# SCH_Phyge-V_1.net
KiCad netlist of a schematic drawn in EasyEDA
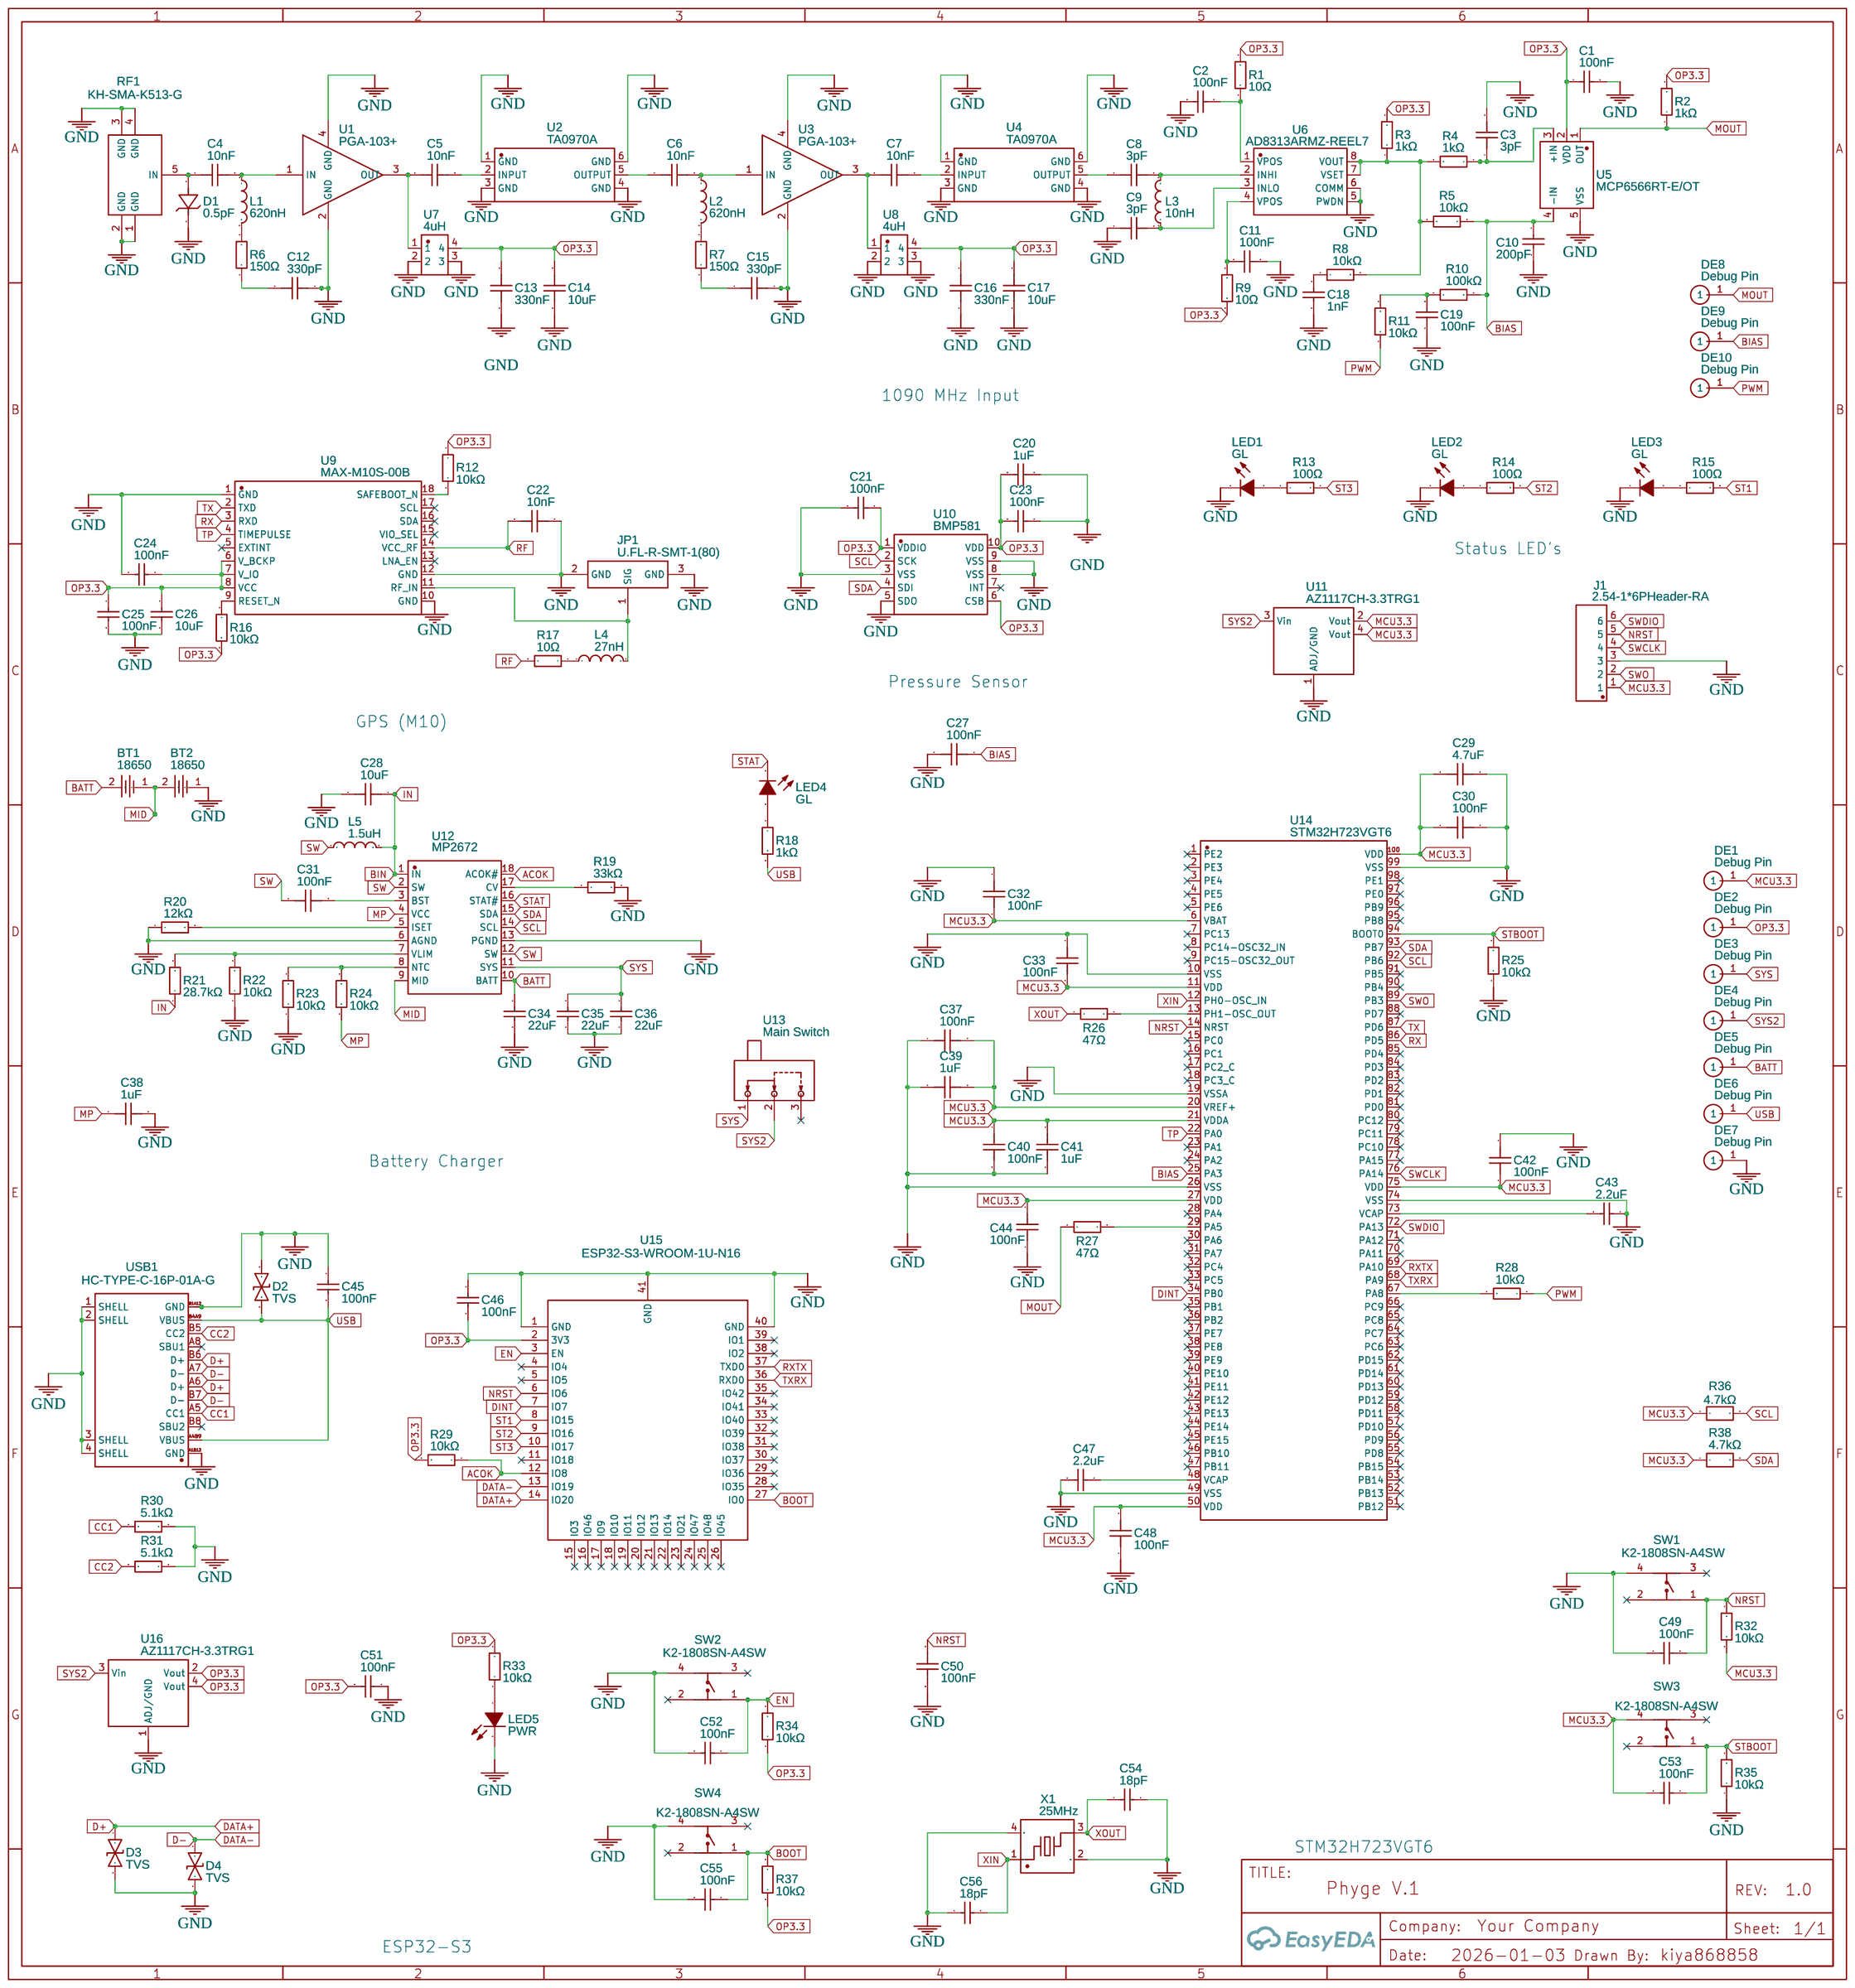
[diagram p0: schematic sheet]

(export (version "E")
  (design (tool "Eeschema 10.0.6"))
  (components
    (comp (ref "BT1")
      (value "18650")
      (fields
        (field (name "Manufacturer Part") "BH-18650-B1BA002")
        (field (name "Manufacturer") "MYOUNG(美阳)")
      )
      (libsource (lib "") (part "BH-18650-B1BA002"))
    )
    (comp (ref "BT2")
      (value "18650")
      (fields
        (field (name "Manufacturer Part") "BH-18650-B1BA002")
        (field (name "Manufacturer") "MYOUNG(美阳)")
      )
      (libsource (lib "") (part "BH-18650-B1BA002"))
    )
    (comp (ref "C1")
      (value "100nF")
      (fields
        (field (name "Manufacturer Part") "CC0603JRX7R9BB104")
        (field (name "Manufacturer") "YAGEO(国巨)")
      )
      (libsource (lib "") (part "CC0603JRX7R9BB104"))
    )
    (comp (ref "C2")
      (value "100nF")
      (fields
        (field (name "Manufacturer Part") "CC0603JRX7R9BB104")
        (field (name "Manufacturer") "YAGEO(国巨)")
      )
      (libsource (lib "") (part "CC0603JRX7R9BB104"))
    )
    (comp (ref "C3")
      (value "3pF")
      (fields (field (name "Manufacturer Part") "CGA3E2C0G1H030CT0Y0N") (field (name "Manufacturer") "TDK"))
      (libsource (lib "") (part "CGA3E2C0G1H030CT0Y0N"))
    )
    (comp (ref "C4")
      (value "10nF")
      (fields
        (field (name "Manufacturer Part") "CC0805JRX7R9BB103")
        (field (name "Manufacturer") "YAGEO(国巨)")
      )
      (libsource (lib "") (part "CC0805JRX7R9BB103"))
    )
    (comp (ref "C5")
      (value "10nF")
      (fields
        (field (name "Manufacturer Part") "CC0805JRX7R9BB103")
        (field (name "Manufacturer") "YAGEO(国巨)")
      )
      (libsource (lib "") (part "CC0805JRX7R9BB103"))
    )
    (comp (ref "C6")
      (value "10nF")
      (fields
        (field (name "Manufacturer Part") "CC0805JRX7R9BB103")
        (field (name "Manufacturer") "YAGEO(国巨)")
      )
      (libsource (lib "") (part "CC0805JRX7R9BB103"))
    )
    (comp (ref "C7")
      (value "10nF")
      (fields
        (field (name "Manufacturer Part") "CC0805JRX7R9BB103")
        (field (name "Manufacturer") "YAGEO(国巨)")
      )
      (libsource (lib "") (part "CC0805JRX7R9BB103"))
    )
    (comp (ref "C8")
      (value "3pF")
      (fields (field (name "Manufacturer Part") "CGA3E2C0G1H030CT0Y0N") (field (name "Manufacturer") "TDK"))
      (libsource (lib "") (part "CGA3E2C0G1H030CT0Y0N_1"))
    )
    (comp (ref "C9")
      (value "3pF")
      (fields (field (name "Manufacturer Part") "CGA3E2C0G1H030CT0Y0N") (field (name "Manufacturer") "TDK"))
      (libsource (lib "") (part "CGA3E2C0G1H030CT0Y0N_1"))
    )
    (comp (ref "C10")
      (value "200pF")
      (fields (field (name "Manufacturer Part") "0603B201K500NT") (field (name "Manufacturer") "FH(风华)"))
      (libsource (lib "") (part "0603B201K500NT"))
    )
    (comp (ref "C11")
      (value "100nF")
      (fields
        (field (name "Manufacturer Part") "CC0603JRX7R9BB104")
        (field (name "Manufacturer") "YAGEO(国巨)")
      )
      (libsource (lib "") (part "CC0603JRX7R9BB104"))
    )
    (comp (ref "C12")
      (value "330pF")
      (fields (field (name "Manufacturer Part") "CGA3E2C0G1H331JT0Y0N") (field (name "Manufacturer") "TDK"))
      (libsource (lib "") (part "CGA3E2C0G1H331JT0Y0N"))
    )
    (comp (ref "C13")
      (value "330nF")
      (fields
        (field (name "Manufacturer Part") "CC1206KRX7R9BB334")
        (field (name "Manufacturer") "YAGEO(国巨)")
      )
      (libsource (lib "") (part "CC1206KRX7R9BB334"))
    )
    (comp (ref "C14")
      (value "10uF")
      (fields
        (field (name "Manufacturer Part") "CL31B106KAHNNNE")
        (field (name "Manufacturer") "SAMSUNG(三星)")
      )
      (libsource (lib "") (part "CL31B106KAHNNNE"))
    )
    (comp (ref "C15")
      (value "330pF")
      (fields (field (name "Manufacturer Part") "CGA3E2C0G1H331JT0Y0N") (field (name "Manufacturer") "TDK"))
      (libsource (lib "") (part "CGA3E2C0G1H331JT0Y0N"))
    )
    (comp (ref "C16")
      (value "330nF")
      (fields
        (field (name "Manufacturer Part") "CC1206KRX7R9BB334")
        (field (name "Manufacturer") "YAGEO(国巨)")
      )
      (libsource (lib "") (part "CC1206KRX7R9BB334"))
    )
    (comp (ref "C17")
      (value "10uF")
      (fields
        (field (name "Manufacturer Part") "CL31B106KAHNNNE")
        (field (name "Manufacturer") "SAMSUNG(三星)")
      )
      (libsource (lib "") (part "CL31B106KAHNNNE"))
    )
    (comp (ref "C18")
      (value "1nF")
      (fields
        (field (name "Manufacturer Part") "CL10B102KB8NNNC")
        (field (name "Manufacturer") "SAMSUNG(三星)")
      )
      (libsource (lib "") (part "CL10B102KB8NNNC"))
    )
    (comp (ref "C19")
      (value "100nF")
      (fields
        (field (name "Manufacturer Part") "CC0603JRX7R9BB104")
        (field (name "Manufacturer") "YAGEO(国巨)")
      )
      (libsource (lib "") (part "CC0603JRX7R9BB104_1"))
    )
    (comp (ref "C20")
      (value "1uF")
      (fields
        (field (name "Manufacturer Part") "CL21B105KOFNNNE")
        (field (name "Manufacturer") "SAMSUNG(三星)")
      )
      (libsource (lib "") (part "CL21B105KOFNNNE"))
    )
    (comp (ref "C21")
      (value "100nF")
      (fields
        (field (name "Manufacturer Part") "GRM188R71C104KA01D")
        (field (name "Manufacturer") "muRata(村田)")
      )
      (libsource (lib "") (part "GRM188R71C104KA01D_1"))
    )
    (comp (ref "C22")
      (value "10nF")
      (fields
        (field (name "Manufacturer Part") "CC0805JRX7R9BB103")
        (field (name "Manufacturer") "YAGEO(国巨)")
      )
      (libsource (lib "") (part "CC0805JRX7R9BB103"))
    )
    (comp (ref "C23")
      (value "100nF")
      (fields
        (field (name "Manufacturer Part") "GRM188R71C104KA01D")
        (field (name "Manufacturer") "muRata(村田)")
      )
      (libsource (lib "") (part "GRM188R71C104KA01D_1"))
    )
    (comp (ref "C24")
      (value "100nF")
      (fields
        (field (name "Manufacturer Part") "GRM188R71C104KA01D")
        (field (name "Manufacturer") "muRata(村田)")
      )
      (libsource (lib "") (part "GRM188R71C104KA01D_1"))
    )
    (comp (ref "C25")
      (value "100nF")
      (fields
        (field (name "Manufacturer Part") "GRM188R71C104KA01D")
        (field (name "Manufacturer") "muRata(村田)")
      )
      (libsource (lib "") (part "GRM188R71C104KA01D_2"))
    )
    (comp (ref "C26")
      (value "10uF")
      (fields (field (name "Manufacturer Part") "C1608X5R1E106MT000E") (field (name "Manufacturer") "TDK"))
      (libsource (lib "") (part "C1608X5R1E106MT000E"))
    )
    (comp (ref "C27")
      (value "100nF")
      (fields
        (field (name "Manufacturer Part") "CC0603KRX7R9BB104")
        (field (name "Manufacturer") "YAGEO(国巨)")
      )
      (libsource (lib "") (part "CC0603KRX7R9BB104"))
    )
    (comp (ref "C28")
      (value "10uF")
      (fields
        (field (name "Manufacturer Part") "CL10A106KP8NNNC")
        (field (name "Manufacturer") "SAMSUNG(三星)")
      )
      (libsource (lib "") (part "CL10A106KP8NNNC"))
    )
    (comp (ref "C29")
      (value "4.7uF")
      (fields
        (field (name "Manufacturer Part") "CL10A475KO8NNNC")
        (field (name "Manufacturer") "SAMSUNG(三星)")
      )
      (libsource (lib "") (part "CL10A475KO8NNNC"))
    )
    (comp (ref "C30")
      (value "100nF")
      (fields
        (field (name "Manufacturer Part") "CC0603KRX7R9BB104")
        (field (name "Manufacturer") "YAGEO(国巨)")
      )
      (libsource (lib "") (part "CC0603KRX7R9BB104"))
    )
    (comp (ref "C31")
      (value "100nF")
      (fields
        (field (name "Manufacturer Part") "CC0603KRX7R9BB104")
        (field (name "Manufacturer") "YAGEO(国巨)")
      )
      (libsource (lib "") (part "CC0603KRX7R9BB104"))
    )
    (comp (ref "C32")
      (value "100nF")
      (fields
        (field (name "Manufacturer Part") "CC0603KRX7R9BB104")
        (field (name "Manufacturer") "YAGEO(国巨)")
      )
      (libsource (lib "") (part "CC0603KRX7R9BB104_2"))
    )
    (comp (ref "C33")
      (value "100nF")
      (fields
        (field (name "Manufacturer Part") "CC0603KRX7R9BB104")
        (field (name "Manufacturer") "YAGEO(国巨)")
      )
      (libsource (lib "") (part "CC0603KRX7R9BB104_2"))
    )
    (comp (ref "C34")
      (value "22uF")
      (fields
        (field (name "Manufacturer Part") "CL31A226KAHNNNE")
        (field (name "Manufacturer") "SAMSUNG(三星)")
      )
      (libsource (lib "") (part "CL31A226KAHNNNE"))
    )
    (comp (ref "C35")
      (value "22uF")
      (fields
        (field (name "Manufacturer Part") "CL31A226KAHNNNE")
        (field (name "Manufacturer") "SAMSUNG(三星)")
      )
      (libsource (lib "") (part "CL31A226KAHNNNE"))
    )
    (comp (ref "C36")
      (value "22uF")
      (fields
        (field (name "Manufacturer Part") "CL31A226KAHNNNE")
        (field (name "Manufacturer") "SAMSUNG(三星)")
      )
      (libsource (lib "") (part "CL31A226KAHNNNE"))
    )
    (comp (ref "C37")
      (value "100nF")
      (fields
        (field (name "Manufacturer Part") "CC0603KRX7R9BB104")
        (field (name "Manufacturer") "YAGEO(国巨)")
      )
      (libsource (lib "") (part "CC0603KRX7R9BB104"))
    )
    (comp (ref "C38")
      (value "1uF")
      (fields
        (field (name "Manufacturer Part") "CL10A105KB8NNNC")
        (field (name "Manufacturer") "SAMSUNG(三星)")
      )
      (libsource (lib "") (part "CL10A105KB8NNNC"))
    )
    (comp (ref "C39")
      (value "1uF")
      (fields
        (field (name "Manufacturer Part") "CL10A105KB8NNNC")
        (field (name "Manufacturer") "SAMSUNG(三星)")
      )
      (libsource (lib "") (part "CL10A105KB8NNNC"))
    )
    (comp (ref "C40")
      (value "100nF")
      (fields
        (field (name "Manufacturer Part") "CC0603KRX7R9BB104")
        (field (name "Manufacturer") "YAGEO(国巨)")
      )
      (libsource (lib "") (part "CC0603KRX7R9BB104_2"))
    )
    (comp (ref "C41")
      (value "1uF")
      (fields
        (field (name "Manufacturer Part") "CL10A105KB8NNNC")
        (field (name "Manufacturer") "SAMSUNG(三星)")
      )
      (libsource (lib "") (part "CL10A105KB8NNNC_1"))
    )
    (comp (ref "C42")
      (value "100nF")
      (fields
        (field (name "Manufacturer Part") "CC0603KRX7R9BB104")
        (field (name "Manufacturer") "YAGEO(国巨)")
      )
      (libsource (lib "") (part "CC0603KRX7R9BB104_1"))
    )
    (comp (ref "C43")
      (value "2.2uF")
      (fields
        (field (name "Manufacturer Part") "CC0603KRX5R6BB225")
        (field (name "Manufacturer") "YAGEO(国巨)")
      )
      (libsource (lib "") (part "CC0603KRX5R6BB225"))
    )
    (comp (ref "C44")
      (value "100nF")
      (fields
        (field (name "Manufacturer Part") "CC0603KRX7R9BB104")
        (field (name "Manufacturer") "YAGEO(国巨)")
      )
      (libsource (lib "") (part "CC0603KRX7R9BB104_1"))
    )
    (comp (ref "C45")
      (value "100nF")
      (fields
        (field (name "Manufacturer Part") "GRM188R71C104KA01D")
        (field (name "Manufacturer") "muRata(村田)")
      )
      (libsource (lib "") (part "GRM188R71C104KA01D_2"))
    )
    (comp (ref "C46")
      (value "100nF")
      (fields
        (field (name "Manufacturer Part") "GRM188R71C104KA01D")
        (field (name "Manufacturer") "muRata(村田)")
      )
      (libsource (lib "") (part "GRM188R71C104KA01D_3"))
    )
    (comp (ref "C47")
      (value "2.2uF")
      (fields
        (field (name "Manufacturer Part") "CC0603KRX5R6BB225")
        (field (name "Manufacturer") "YAGEO(国巨)")
      )
      (libsource (lib "") (part "CC0603KRX5R6BB225_1"))
    )
    (comp (ref "C48")
      (value "100nF")
      (fields
        (field (name "Manufacturer Part") "CC0603KRX7R9BB104")
        (field (name "Manufacturer") "YAGEO(国巨)")
      )
      (libsource (lib "") (part "CC0603KRX7R9BB104_1"))
    )
    (comp (ref "C49")
      (value "100nF")
      (fields
        (field (name "Manufacturer Part") "GRM188R71C104KA01D")
        (field (name "Manufacturer") "muRata(村田)")
      )
      (libsource (lib "") (part "GRM188R71C104KA01D"))
    )
    (comp (ref "C50")
      (value "100nF")
      (fields
        (field (name "Manufacturer Part") "CC0603KRX7R9BB104")
        (field (name "Manufacturer") "YAGEO(国巨)")
      )
      (libsource (lib "") (part "CC0603KRX7R9BB104_1"))
    )
    (comp (ref "C51")
      (value "100nF")
      (fields
        (field (name "Manufacturer Part") "GRM188R71C104KA01D")
        (field (name "Manufacturer") "muRata(村田)")
      )
      (libsource (lib "") (part "GRM188R71C104KA01D"))
    )
    (comp (ref "C52")
      (value "100nF")
      (fields
        (field (name "Manufacturer Part") "GRM188R71C104KA01D")
        (field (name "Manufacturer") "muRata(村田)")
      )
      (libsource (lib "") (part "GRM188R71C104KA01D"))
    )
    (comp (ref "C53")
      (value "100nF")
      (fields
        (field (name "Manufacturer Part") "GRM188R71C104KA01D")
        (field (name "Manufacturer") "muRata(村田)")
      )
      (libsource (lib "") (part "GRM188R71C104KA01D"))
    )
    (comp (ref "C54")
      (value "18pF")
      (fields
        (field (name "Manufacturer Part") "CL10C180JB8NNNC")
        (field (name "Manufacturer") "SAMSUNG(三星)")
      )
      (libsource (lib "") (part "CL10C180JB8NNNC"))
    )
    (comp (ref "C55")
      (value "100nF")
      (fields
        (field (name "Manufacturer Part") "GRM188R71C104KA01D")
        (field (name "Manufacturer") "muRata(村田)")
      )
      (libsource (lib "") (part "GRM188R71C104KA01D"))
    )
    (comp (ref "C56")
      (value "18pF")
      (fields
        (field (name "Manufacturer Part") "CL10C180JB8NNNC")
        (field (name "Manufacturer") "SAMSUNG(三星)")
      )
      (libsource (lib "") (part "CL10C180JB8NNNC"))
    )
    (comp (ref "D1")
      (value "0.5pF")
      (fields (field (name "Manufacturer Part") "ESD9L5.0") (field (name "Manufacturer") "Wild Goose(威谷)"))
      (libsource (lib "") (part "ESD9L5.0"))
    )
    (comp (ref "D2")
      (value "TVS")
      (fields (field (name "Manufacturer Part") "LESD5D5.0CT1G") (field (name "Manufacturer") "LRC(乐山无线电)"))
      (libsource (lib "") (part "LESD5D5.0CT1G"))
    )
    (comp (ref "D3")
      (value "TVS")
      (fields (field (name "Manufacturer Part") "LESD5D5.0CT1G") (field (name "Manufacturer") "LRC(乐山无线电)"))
      (libsource (lib "") (part "LESD5D5.0CT1G"))
    )
    (comp (ref "D4")
      (value "TVS")
      (fields (field (name "Manufacturer Part") "LESD5D5.0CT1G") (field (name "Manufacturer") "LRC(乐山无线电)"))
      (libsource (lib "") (part "LESD5D5.0CT1G"))
    )
    (comp (ref "DE1") (value "Debug Pin") (libsource (lib "") (part "Debug Pin")))
    (comp (ref "DE2") (value "Debug Pin") (libsource (lib "") (part "Debug Pin")))
    (comp (ref "DE3") (value "Debug Pin") (libsource (lib "") (part "Debug Pin")))
    (comp (ref "DE4") (value "Debug Pin") (libsource (lib "") (part "Debug Pin")))
    (comp (ref "DE5") (value "Debug Pin") (libsource (lib "") (part "Debug Pin")))
    (comp (ref "DE6") (value "Debug Pin") (libsource (lib "") (part "Debug Pin")))
    (comp (ref "DE7") (value "Debug Pin") (libsource (lib "") (part "Debug Pin")))
    (comp (ref "DE8") (value "Debug Pin") (libsource (lib "") (part "Debug Pin")))
    (comp (ref "DE9") (value "Debug Pin") (libsource (lib "") (part "Debug Pin")))
    (comp (ref "DE10") (value "Debug Pin") (libsource (lib "") (part "Debug Pin")))
    (comp (ref "J1")
      (value "2.54-1*6PHeader-RA")
      (fields
        (field (name "Manufacturer Part") "2.54-1*6P反弯排针")
        (field (name "Manufacturer") "BOOMELE(博穆精密)")
      )
      (libsource (lib "") (part "2.54-1*6PHeader-RA"))
    )
    (comp (ref "JP1")
      (value "U.FL-R-SMT-1(80)")
      (fields (field (name "Manufacturer") "HRS(广濑)"))
      (libsource (lib "") (part "U.FL-R-SMT-1(80)"))
    )
    (comp (ref "L1")
      (value "620nH")
      (fields (field (name "Manufacturer Part") "AHW2012C-R62JTF") (field (name "Manufacturer") "APV(爱普微)"))
      (libsource (lib "") (part "AHW2012C-R62JTF"))
    )
    (comp (ref "L2")
      (value "620nH")
      (fields (field (name "Manufacturer Part") "AHW2012C-R62JTF") (field (name "Manufacturer") "APV(爱普微)"))
      (libsource (lib "") (part "AHW2012C-R62JTF"))
    )
    (comp (ref "L3")
      (value "10nH")
      (fields (field (name "Manufacturer Part") "AHW2012C-10NJTF") (field (name "Manufacturer") "APV(爱普微)"))
      (libsource (lib "") (part "AHW2012C-10NJTF"))
    )
    (comp (ref "L4")
      (value "27nH")
      (fields (field (name "Manufacturer Part") "MLK1005S27NJT000") (field (name "Manufacturer") "TDK"))
      (libsource (lib "") (part "MLK1005S27NJT000"))
    )
    (comp (ref "L5")
      (value "1.5uH")
      (fields (field (name "Manufacturer Part") "CYA0630-1.5UH") (field (name "Manufacturer") "SHOU HAN(首韩)"))
      (libsource (lib "") (part "CYA0630-1.5UH"))
    )
    (comp (ref "LED1")
      (value "GL")
      (fields
        (field (name "Manufacturer Part") "19-217/GHC-YR1S2/3T")
        (field (name "Manufacturer") "EVERLIGHT(亿光)")
      )
      (libsource (lib "") (part "19-217/GHC-YR1S2/3T"))
    )
    (comp (ref "LED2")
      (value "GL")
      (fields
        (field (name "Manufacturer Part") "19-217/GHC-YR1S2/3T")
        (field (name "Manufacturer") "EVERLIGHT(亿光)")
      )
      (libsource (lib "") (part "19-217/GHC-YR1S2/3T"))
    )
    (comp (ref "LED3")
      (value "GL")
      (fields
        (field (name "Manufacturer Part") "19-217/GHC-YR1S2/3T")
        (field (name "Manufacturer") "EVERLIGHT(亿光)")
      )
      (libsource (lib "") (part "19-217/GHC-YR1S2/3T"))
    )
    (comp (ref "LED4")
      (value "GL")
      (fields
        (field (name "Manufacturer Part") "19-217/GHC-YR1S2/3T")
        (field (name "Manufacturer") "EVERLIGHT(亿光)")
      )
      (libsource (lib "") (part "19-217/GHC-YR1S2/3T_1"))
    )
    (comp (ref "LED5")
      (value "PWR")
      (fields (field (name "Manufacturer Part") "NCD0805R1") (field (name "Manufacturer") "国星光电"))
      (libsource (lib "") (part "FC-2012HRK-620D"))
    )
    (comp (ref "R1")
      (value "10Ω")
      (fields
        (field (name "Manufacturer Part") "0603WAF100JT5E")
        (field (name "Manufacturer") "UNI-ROYAL(厚声)")
      )
      (libsource (lib "") (part "0603WAF100JT5E_1"))
    )
    (comp (ref "R2")
      (value "1kΩ")
      (fields
        (field (name "Manufacturer Part") "0603WAF1001T5E")
        (field (name "Manufacturer") "UNI-ROYAL(厚声)")
      )
      (libsource (lib "") (part "0603WAF1001T5E_1"))
    )
    (comp (ref "R3")
      (value "1kΩ")
      (fields
        (field (name "Manufacturer Part") "0603WAF1001T5E")
        (field (name "Manufacturer") "UNI-ROYAL(厚声)")
      )
      (libsource (lib "") (part "0603WAF1001T5E_1"))
    )
    (comp (ref "R4")
      (value "1kΩ")
      (fields
        (field (name "Manufacturer Part") "0603WAF1001T5E")
        (field (name "Manufacturer") "UNI-ROYAL(厚声)")
      )
      (libsource (lib "") (part "0603WAF1001T5E"))
    )
    (comp (ref "R5")
      (value "10kΩ")
      (fields
        (field (name "Manufacturer Part") "0603WAF1002T5E")
        (field (name "Manufacturer") "UNI-ROYAL(厚声)")
      )
      (libsource (lib "") (part "0603WAF1002T5E"))
    )
    (comp (ref "R6")
      (value "150Ω")
      (fields
        (field (name "Manufacturer Part") "0603WAF1500T5E")
        (field (name "Manufacturer") "UNI-ROYAL(厚声)")
      )
      (libsource (lib "") (part "0603WAF1500T5E"))
    )
    (comp (ref "R7")
      (value "150Ω")
      (fields
        (field (name "Manufacturer Part") "0603WAF1500T5E")
        (field (name "Manufacturer") "UNI-ROYAL(厚声)")
      )
      (libsource (lib "") (part "0603WAF1500T5E"))
    )
    (comp (ref "R8")
      (value "10kΩ")
      (fields
        (field (name "Manufacturer Part") "0603WAF1002T5E")
        (field (name "Manufacturer") "UNI-ROYAL(厚声)")
      )
      (libsource (lib "") (part "0603WAF1002T5E"))
    )
    (comp (ref "R9")
      (value "10Ω")
      (fields
        (field (name "Manufacturer Part") "0603WAF100JT5E")
        (field (name "Manufacturer") "UNI-ROYAL(厚声)")
      )
      (libsource (lib "") (part "0603WAF100JT5E_1"))
    )
    (comp (ref "R10")
      (value "100kΩ")
      (fields
        (field (name "Manufacturer Part") "0603WAF1003T5E")
        (field (name "Manufacturer") "UNI-ROYAL(厚声)")
      )
      (libsource (lib "") (part "0603WAF1003T5E"))
    )
    (comp (ref "R11")
      (value "10kΩ")
      (fields
        (field (name "Manufacturer Part") "0603WAF1002T5E")
        (field (name "Manufacturer") "UNI-ROYAL(厚声)")
      )
      (libsource (lib "") (part "0603WAF1002T5E_1"))
    )
    (comp (ref "R12")
      (value "10kΩ")
      (fields
        (field (name "Manufacturer Part") "0603WAJ0103T5E")
        (field (name "Manufacturer") "UNI-ROYAL(厚声)")
      )
      (libsource (lib "") (part "0603WAJ0103T5E_1"))
    )
    (comp (ref "R13")
      (value "100Ω")
      (fields (field (name "Manufacturer Part") "RT0603BRD07100RL") (field (name "Manufacturer") "YAGEO(国巨)"))
      (libsource (lib "") (part "RT0603BRD07100RL"))
    )
    (comp (ref "R14")
      (value "100Ω")
      (fields (field (name "Manufacturer Part") "RT0603BRD07100RL") (field (name "Manufacturer") "YAGEO(国巨)"))
      (libsource (lib "") (part "RT0603BRD07100RL"))
    )
    (comp (ref "R15")
      (value "100Ω")
      (fields (field (name "Manufacturer Part") "RT0603BRD07100RL") (field (name "Manufacturer") "YAGEO(国巨)"))
      (libsource (lib "") (part "RT0603BRD07100RL"))
    )
    (comp (ref "R16")
      (value "10kΩ")
      (fields
        (field (name "Manufacturer Part") "0603WAJ0103T5E")
        (field (name "Manufacturer") "UNI-ROYAL(厚声)")
      )
      (libsource (lib "") (part "0603WAJ0103T5E_1"))
    )
    (comp (ref "R17")
      (value "10Ω")
      (fields
        (field (name "Manufacturer Part") "0603WAF100JT5E")
        (field (name "Manufacturer") "UNI-ROYAL(厚声)")
      )
      (libsource (lib "") (part "0603WAF100JT5E"))
    )
    (comp (ref "R18")
      (value "1kΩ")
      (fields (field (name "Manufacturer Part") "RC0603JR-071KL") (field (name "Manufacturer") "YAGEO(国巨)"))
      (libsource (lib "") (part "RC0603JR-071KL"))
    )
    (comp (ref "R19")
      (value "33kΩ")
      (fields
        (field (name "Manufacturer Part") "0603WAF3302T5E")
        (field (name "Manufacturer") "UNI-ROYAL(厚声)")
      )
      (libsource (lib "") (part "0603WAF3302T5E"))
    )
    (comp (ref "R20")
      (value "12kΩ")
      (fields
        (field (name "Manufacturer Part") "0603WAF1202T5E")
        (field (name "Manufacturer") "UNI-ROYAL(厚声)")
      )
      (libsource (lib "") (part "0603WAF1202T5E"))
    )
    (comp (ref "R21")
      (value "28.7kΩ")
      (fields
        (field (name "Manufacturer Part") "0603WAF2872T5E")
        (field (name "Manufacturer") "UNI-ROYAL(厚声)")
      )
      (libsource (lib "") (part "0603WAF2872T5E"))
    )
    (comp (ref "R22")
      (value "10kΩ")
      (fields
        (field (name "Manufacturer Part") "0603WAJ0103T5E")
        (field (name "Manufacturer") "UNI-ROYAL(厚声)")
      )
      (libsource (lib "") (part "0603WAJ0103T5E"))
    )
    (comp (ref "R23")
      (value "10kΩ")
      (fields
        (field (name "Manufacturer Part") "0603WAJ0103T5E")
        (field (name "Manufacturer") "UNI-ROYAL(厚声)")
      )
      (libsource (lib "") (part "0603WAJ0103T5E"))
    )
    (comp (ref "R24")
      (value "10kΩ")
      (fields
        (field (name "Manufacturer Part") "0603WAJ0103T5E")
        (field (name "Manufacturer") "UNI-ROYAL(厚声)")
      )
      (libsource (lib "") (part "0603WAJ0103T5E"))
    )
    (comp (ref "R25")
      (value "10kΩ")
      (fields
        (field (name "Manufacturer Part") "0603WAJ0103T5E")
        (field (name "Manufacturer") "UNI-ROYAL(厚声)")
      )
      (libsource (lib "") (part "0603WAJ0103T5E"))
    )
    (comp (ref "R26")
      (value "47Ω")
      (fields
        (field (name "Manufacturer Part") "0603WAF470JT5E")
        (field (name "Manufacturer") "UNI-ROYAL(厚声)")
      )
      (libsource (lib "") (part "0603WAF470JT5E"))
    )
    (comp (ref "R27")
      (value "47Ω")
      (fields
        (field (name "Manufacturer Part") "0603WAF470JT5E")
        (field (name "Manufacturer") "UNI-ROYAL(厚声)")
      )
      (libsource (lib "") (part "0603WAF470JT5E"))
    )
    (comp (ref "R28")
      (value "10kΩ")
      (fields
        (field (name "Manufacturer Part") "0603WAJ0103T5E")
        (field (name "Manufacturer") "UNI-ROYAL(厚声)")
      )
      (libsource (lib "") (part "0603WAJ0103T5E_2"))
    )
    (comp (ref "R29")
      (value "10kΩ")
      (fields
        (field (name "Manufacturer Part") "0603WAJ0103T5E")
        (field (name "Manufacturer") "UNI-ROYAL(厚声)")
      )
      (libsource (lib "") (part "0603WAJ0103T5E_2"))
    )
    (comp (ref "R30")
      (value "5.1kΩ")
      (fields (field (name "Manufacturer Part") "RMC08055.1K1%N") (field (name "Manufacturer") "Tyohm(幸亚电阻)"))
      (libsource (lib "") (part "RMC08055.1K1%N"))
    )
    (comp (ref "R31")
      (value "5.1kΩ")
      (fields (field (name "Manufacturer Part") "RMC08055.1K1%N") (field (name "Manufacturer") "Tyohm(幸亚电阻)"))
      (libsource (lib "") (part "RMC08055.1K1%N"))
    )
    (comp (ref "R32")
      (value "10kΩ")
      (fields
        (field (name "Manufacturer Part") "0603WAJ0103T5E")
        (field (name "Manufacturer") "UNI-ROYAL(厚声)")
      )
      (libsource (lib "") (part "0603WAJ0103T5E"))
    )
    (comp (ref "R33")
      (value "10kΩ")
      (fields
        (field (name "Manufacturer Part") "0603WAJ0103T5E")
        (field (name "Manufacturer") "UNI-ROYAL(厚声)")
      )
      (libsource (lib "") (part "0603WAJ0103T5E"))
    )
    (comp (ref "R34")
      (value "10kΩ")
      (fields
        (field (name "Manufacturer Part") "0603WAJ0103T5E")
        (field (name "Manufacturer") "UNI-ROYAL(厚声)")
      )
      (libsource (lib "") (part "0603WAJ0103T5E"))
    )
    (comp (ref "R35")
      (value "10kΩ")
      (fields
        (field (name "Manufacturer Part") "0603WAJ0103T5E")
        (field (name "Manufacturer") "UNI-ROYAL(厚声)")
      )
      (libsource (lib "") (part "0603WAJ0103T5E"))
    )
    (comp (ref "R36")
      (value "4.7kΩ")
      (fields (field (name "Manufacturer Part") "ERJ6RBD4701V") (field (name "Manufacturer") "PANASONIC(松下)"))
      (libsource (lib "") (part "ERJ6RBD4701V"))
    )
    (comp (ref "R37")
      (value "10kΩ")
      (fields
        (field (name "Manufacturer Part") "0603WAJ0103T5E")
        (field (name "Manufacturer") "UNI-ROYAL(厚声)")
      )
      (libsource (lib "") (part "0603WAJ0103T5E"))
    )
    (comp (ref "R38")
      (value "4.7kΩ")
      (fields (field (name "Manufacturer Part") "ERJ6RBD4701V") (field (name "Manufacturer") "PANASONIC(松下)"))
      (libsource (lib "") (part "ERJ6RBD4701V"))
    )
    (comp (ref "RF1")
      (value "KH-SMA-K513-G")
      (fields (field (name "Manufacturer") "kinghelm(金航标)"))
      (libsource (lib "") (part "KH-SMA-K513-G"))
    )
    (comp (ref "SW1")
      (value "K2-1808SN-A4SW")
      (fields (field (name "Manufacturer Part") "K2-1808SN-A4SW-01") (field (name "Manufacturer") "韩国韩荣"))
      (libsource (lib "") (part "K2-1808SN-A4SW"))
    )
    (comp (ref "SW2")
      (value "K2-1808SN-A4SW")
      (fields (field (name "Manufacturer Part") "K2-1808SN-A4SW-01") (field (name "Manufacturer") "韩国韩荣"))
      (libsource (lib "") (part "K2-1808SN-A4SW"))
    )
    (comp (ref "SW3")
      (value "K2-1808SN-A4SW")
      (fields (field (name "Manufacturer Part") "K2-1808SN-A4SW-01") (field (name "Manufacturer") "韩国韩荣"))
      (libsource (lib "") (part "K2-1808SN-A4SW"))
    )
    (comp (ref "SW4")
      (value "K2-1808SN-A4SW")
      (fields (field (name "Manufacturer Part") "K2-1808SN-A4SW-01") (field (name "Manufacturer") "韩国韩荣"))
      (libsource (lib "") (part "K2-1808SN-A4SW"))
    )
    (comp (ref "U1")
      (value "PGA-103+")
      (fields (field (name "Manufacturer") "Mini-Circuits"))
      (libsource (lib "") (part "PGA-103+ (1)"))
    )
    (comp (ref "U2")
      (value "TA0970A")
      (fields (field (name "Manufacturer") "TST(嘉硕)"))
      (libsource (lib "") (part "TA0970A"))
    )
    (comp (ref "U3")
      (value "PGA-103+")
      (fields (field (name "Manufacturer") "Mini-Circuits"))
      (libsource (lib "") (part "PGA-103+ (1)"))
    )
    (comp (ref "U4")
      (value "TA0970A")
      (fields (field (name "Manufacturer") "TST(嘉硕)"))
      (libsource (lib "") (part "TA0970A"))
    )
    (comp (ref "U5")
      (value "MCP6566RT-E/OT")
      (fields (field (name "Manufacturer") "MICROCHIP(美国微芯)"))
      (libsource (lib "") (part "MCP6566RT-E/OT"))
    )
    (comp (ref "U6")
      (value "AD8313ARMZ-REEL7")
      (fields (field (name "Manufacturer") "ADI(亚德诺)"))
      (libsource (lib "") (part "AD8313ARMZ-REEL7"))
    )
    (comp (ref "U7")
      (value "4uH")
      (fields (field (name "Manufacturer Part") "TCCH-80+") (field (name "Manufacturer") "Mini-Circuits"))
      (libsource (lib "") (part "TCCH-80+"))
    )
    (comp (ref "U8")
      (value "4uH")
      (fields (field (name "Manufacturer Part") "TCCH-80+") (field (name "Manufacturer") "Mini-Circuits"))
      (libsource (lib "") (part "TCCH-80+"))
    )
    (comp (ref "U9")
      (value "MAX-M10S-00B")
      (fields (field (name "Manufacturer") "U-BLOX"))
      (libsource (lib "") (part "MAX-M10S-00B"))
    )
    (comp (ref "U10")
      (value "BMP581")
      (fields (field (name "Manufacturer") "Bosch(博世)"))
      (libsource (lib "") (part "BMP581"))
    )
    (comp (ref "U11")
      (value "AZ1117CH-3.3TRG1")
      (fields (field (name "Manufacturer") "DIODES(美台)"))
      (libsource (lib "") (part "AZ1117CH-3.3TRG1"))
    )
    (comp (ref "U12")
      (value "MP2672")
      (fields (field (name "Manufacturer Part") "MP2672AGD-0000-Z") (field (name "Manufacturer") "MPS(芯源)"))
      (libsource (lib "") (part "MP2672AGD-0000-Z"))
    )
    (comp (ref "U13")
      (value "Main Switch")
      (fields (field (name "Manufacturer Part") "SS-12D06-G050") (field (name "Manufacturer") "G-Switch(品赞)"))
      (libsource (lib "") (part "SS-12D06-G050"))
    )
    (comp (ref "U14")
      (value "STM32H723VGT6")
      (fields (field (name "Manufacturer") "ST(意法半导体)"))
      (libsource (lib "") (part "STM32H723VGT6"))
    )
    (comp (ref "U15")
      (value "ESP32-S3-WROOM-1U-N16")
      (fields (field (name "Manufacturer") "ESPRESSIF(乐鑫)"))
      (libsource (lib "") (part "ESP32-S3-WROOM-1U-N16"))
    )
    (comp (ref "U16")
      (value "AZ1117CH-3.3TRG1")
      (fields (field (name "Manufacturer") "DIODES(美台)"))
      (libsource (lib "") (part "AZ1117CH-3.3TRG1"))
    )
    (comp (ref "USB1")
      (value "HC-TYPE-C-16P-01A-G")
      (fields (field (name "Manufacturer") "HCTL(华灿天禄)"))
      (libsource (lib "") (part "HC-TYPE-C-16P-01A-G"))
    )
    (comp (ref "X1")
      (value "25MHz")
      (fields
        (field (name "Manufacturer Part") "XXDBBCNANF-25.000000MHZ")
        (field (name "Manufacturer") "TAITIEN(泰艺电子)")
      )
      (libsource (lib "") (part "XXDBBCNANF-25.000000MHZ"))
    )
  )
  (nets
    (net (code "1") (name "ACOK") (class "Default")
      (node (ref "R29") (pin "1") (pinfunction "1_1") (pintype "input"))
      (node (ref "U12") (pin "18") (pinfunction "ACOK#_18") (pintype "unspecified"))
      (node (ref "U15") (pin "12") (pinfunction "IO8_12") (pintype "unspecified"))
    )
    (net (code "2") (name "BATT") (class "Default")
      (node (ref "BT1") (pin "2") (pinfunction "2_2") (pintype "input"))
      (node (ref "C34") (pin "2") (pinfunction "2_2") (pintype "input"))
      (node (ref "DE5") (pin "1") (pinfunction "1_1") (pintype "unspecified"))
      (node (ref "U12") (pin "10") (pinfunction "BATT_10") (pintype "unspecified"))
    )
    (net (code "3") (name "BIAS") (class "Default")
      (node (ref "C10") (pin "2") (pinfunction "2_2") (pintype "input"))
      (node (ref "C27") (pin "2") (pinfunction "2_2") (pintype "unspecified"))
      (node (ref "DE9") (pin "1") (pinfunction "1_1") (pintype "unspecified"))
      (node (ref "R10") (pin "2") (pinfunction "2_2") (pintype "input"))
      (node (ref "R5") (pin "2") (pinfunction "2_2") (pintype "input"))
      (node (ref "U14") (pin "25") (pinfunction "PA3_25") (pintype "unspecified"))
      (node (ref "U5") (pin "4") (pinfunction "-IN_4") (pintype "unspecified"))
    )
    (net (code "4") (name "BIN") (class "Default")
      (node (ref "C28") (pin "2") (pinfunction "2_2") (pintype "unspecified"))
      (node (ref "L5") (pin "2") (pinfunction "2_2") (pintype "unspecified"))
      (node (ref "R21") (pin "1") (pinfunction "1_1") (pintype "input"))
      (node (ref "U12") (pin "1") (pinfunction "IN_1") (pintype "unspecified"))
    )
    (net (code "5") (name "BOOT") (class "Default")
      (node (ref "C55") (pin "1") (pinfunction "1_1") (pintype "input"))
      (node (ref "R37") (pin "2") (pinfunction "2_2") (pintype "input"))
      (node (ref "SW4") (pin "1") (pinfunction "1_1") (pintype "unspecified"))
      (node (ref "U15") (pin "27") (pinfunction "IO0_27") (pintype "unspecified"))
    )
    (net (code "6") (name "CC1") (class "Default")
      (node (ref "R30") (pin "1") (pinfunction "1_1") (pintype "unspecified"))
      (node (ref "USB1") (pin "A5") (pinfunction "CC1_A5") (pintype "unspecified"))
    )
    (net (code "7") (name "CC2") (class "Default")
      (node (ref "R31") (pin "1") (pinfunction "1_1") (pintype "unspecified"))
      (node (ref "USB1") (pin "B5") (pinfunction "CC2_B5") (pintype "unspecified"))
    )
    (net (code "8") (name "D+") (class "Default")
      (node (ref "D3") (pin "1") (pinfunction "1_1") (pintype "unspecified"))
      (node (ref "U15") (pin "14") (pinfunction "IO20_14") (pintype "unspecified"))
      (node (ref "USB1") (pin "A6") (pinfunction "D+_A6") (pintype "unspecified"))
      (node (ref "USB1") (pin "B6") (pinfunction "D+_B6") (pintype "unspecified"))
    )
    (net (code "9") (name "D-") (class "Default")
      (node (ref "D4") (pin "1") (pinfunction "1_1") (pintype "unspecified"))
      (node (ref "U15") (pin "13") (pinfunction "IO19_13") (pintype "unspecified"))
      (node (ref "USB1") (pin "A7") (pinfunction "D-_A7") (pintype "unspecified"))
      (node (ref "USB1") (pin "B7") (pinfunction "D-_B7") (pintype "unspecified"))
    )
    (net (code "10") (name "DINT") (class "Default")
      (node (ref "U14") (pin "34") (pinfunction "PB0_34") (pintype "unspecified"))
      (node (ref "U15") (pin "7") (pinfunction "IO7_7") (pintype "unspecified"))
    )
    (net (code "11") (name "EN") (class "Default")
      (node (ref "C52") (pin "1") (pinfunction "1_1") (pintype "input"))
      (node (ref "R34") (pin "2") (pinfunction "2_2") (pintype "input"))
      (node (ref "SW2") (pin "1") (pinfunction "1_1") (pintype "unspecified"))
      (node (ref "U15") (pin "3") (pinfunction "EN_3") (pintype "unspecified"))
    )
    (net (code "12") (name "GND") (class "Default")
      (node (ref "BT2") (pin "1") (pinfunction "1_1") (pintype "input"))
      (node (ref "C1") (pin "2") (pinfunction "2_2") (pintype "input"))
      (node (ref "C10") (pin "1") (pinfunction "1_1") (pintype "input"))
      (node (ref "C11") (pin "2") (pinfunction "2_2") (pintype "input"))
      (node (ref "C12") (pin "1") (pinfunction "1_1") (pintype "unspecified"))
      (node (ref "C13") (pin "1") (pinfunction "1_1") (pintype "unspecified"))
      (node (ref "C14") (pin "1") (pinfunction "1_1") (pintype "unspecified"))
      (node (ref "C15") (pin "1") (pinfunction "1_1") (pintype "unspecified"))
      (node (ref "C16") (pin "1") (pinfunction "1_1") (pintype "unspecified"))
      (node (ref "C17") (pin "1") (pinfunction "1_1") (pintype "unspecified"))
      (node (ref "C18") (pin "1") (pinfunction "1_1") (pintype "input"))
      (node (ref "C19") (pin "1") (pinfunction "1_1") (pintype "input"))
      (node (ref "C2") (pin "1") (pinfunction "1_1") (pintype "input"))
      (node (ref "C20") (pin "2") (pinfunction "2_2") (pintype "input"))
      (node (ref "C21") (pin "1") (pinfunction "1_1") (pintype "input"))
      (node (ref "C22") (pin "2") (pinfunction "2_2") (pintype "unspecified"))
      (node (ref "C23") (pin "2") (pinfunction "2_2") (pintype "input"))
      (node (ref "C24") (pin "1") (pinfunction "1_1") (pintype "input"))
      (node (ref "C25") (pin "2") (pinfunction "2_2") (pintype "input"))
      (node (ref "C26") (pin "2") (pinfunction "2_2") (pintype "input"))
      (node (ref "C27") (pin "1") (pinfunction "1_1") (pintype "unspecified"))
      (node (ref "C28") (pin "1") (pinfunction "1_1") (pintype "unspecified"))
      (node (ref "C29") (pin "2") (pinfunction "2_2") (pintype "unspecified"))
      (node (ref "C3") (pin "2") (pinfunction "2_2") (pintype "unspecified"))
      (node (ref "C30") (pin "2") (pinfunction "2_2") (pintype "unspecified"))
      (node (ref "C32") (pin "1") (pinfunction "1_1") (pintype "unspecified"))
      (node (ref "C33") (pin "1") (pinfunction "1_1") (pintype "unspecified"))
      (node (ref "C34") (pin "1") (pinfunction "1_1") (pintype "input"))
      (node (ref "C35") (pin "1") (pinfunction "1_1") (pintype "input"))
      (node (ref "C36") (pin "1") (pinfunction "1_1") (pintype "input"))
      (node (ref "C37") (pin "1") (pinfunction "1_1") (pintype "unspecified"))
      (node (ref "C38") (pin "2") (pinfunction "2_2") (pintype "unspecified"))
      (node (ref "C39") (pin "1") (pinfunction "1_1") (pintype "unspecified"))
      (node (ref "C40") (pin "2") (pinfunction "2_2") (pintype "unspecified"))
      (node (ref "C41") (pin "2") (pinfunction "2_2") (pintype "unspecified"))
      (node (ref "C42") (pin "2") (pinfunction "2_2") (pintype "unspecified"))
      (node (ref "C43") (pin "1") (pinfunction "1_1") (pintype "input"))
      (node (ref "C44") (pin "1") (pinfunction "1_1") (pintype "unspecified"))
      (node (ref "C45") (pin "1") (pinfunction "1_1") (pintype "input"))
      (node (ref "C46") (pin "2") (pinfunction "2_2") (pintype "input"))
      (node (ref "C47") (pin "1") (pinfunction "1_1") (pintype "input"))
      (node (ref "C48") (pin "1") (pinfunction "1_1") (pintype "unspecified"))
      (node (ref "C49") (pin "2") (pinfunction "2_2") (pintype "input"))
      (node (ref "C50") (pin "1") (pinfunction "1_1") (pintype "unspecified"))
      (node (ref "C51") (pin "1") (pinfunction "1_1") (pintype "input"))
      (node (ref "C52") (pin "2") (pinfunction "2_2") (pintype "input"))
      (node (ref "C54") (pin "2") (pinfunction "2_2") (pintype "input"))
      (node (ref "C55") (pin "2") (pinfunction "2_2") (pintype "input"))
      (node (ref "C56") (pin "1") (pinfunction "1_1") (pintype "input"))
      (node (ref "C9") (pin "1") (pinfunction "1_1") (pintype "unspecified"))
      (node (ref "D1") (pin "1") (pinfunction "C_1") (pintype "unspecified"))
      (node (ref "D2") (pin "1") (pinfunction "1_1") (pintype "unspecified"))
      (node (ref "D3") (pin "2") (pinfunction "2_2") (pintype "unspecified"))
      (node (ref "D4") (pin "2") (pinfunction "2_2") (pintype "unspecified"))
      (node (ref "DE7") (pin "1") (pinfunction "1_1") (pintype "unspecified"))
      (node (ref "J1") (pin "3") (pinfunction "3_3") (pintype "unspecified"))
      (node (ref "JP1") (pin "2") (pinfunction "GND_2") (pintype "unspecified"))
      (node (ref "JP1") (pin "3") (pinfunction "GND_3") (pintype "unspecified"))
      (node (ref "LED1") (pin "1") (pinfunction "C_1") (pintype "input"))
      (node (ref "LED2") (pin "1") (pinfunction "C_1") (pintype "input"))
      (node (ref "LED3") (pin "1") (pinfunction "C_1") (pintype "input"))
      (node (ref "LED5") (pin "2") (pinfunction "-_2") (pintype "unspecified"))
      (node (ref "R19") (pin "2") (pinfunction "2_2") (pintype "input"))
      (node (ref "R20") (pin "1") (pinfunction "1_1") (pintype "input"))
      (node (ref "R22") (pin "1") (pinfunction "1_1") (pintype "input"))
      (node (ref "R23") (pin "1") (pinfunction "1_1") (pintype "input"))
      (node (ref "R25") (pin "1") (pinfunction "1_1") (pintype "input"))
      (node (ref "R30") (pin "2") (pinfunction "2_2") (pintype "unspecified"))
      (node (ref "R31") (pin "2") (pinfunction "2_2") (pintype "unspecified"))
      (node (ref "R35") (pin "1") (pinfunction "1_1") (pintype "input"))
      (node (ref "RF1") (pin "1") (pinfunction "GND_1") (pintype "unspecified"))
      (node (ref "RF1") (pin "2") (pinfunction "GND_2") (pintype "unspecified"))
      (node (ref "RF1") (pin "3") (pinfunction "GND_3") (pintype "unspecified"))
      (node (ref "RF1") (pin "4") (pinfunction "GND_4") (pintype "unspecified"))
      (node (ref "SW1") (pin "4") (pinfunction "4_4") (pintype "unspecified"))
      (node (ref "SW2") (pin "4") (pinfunction "4_4") (pintype "unspecified"))
      (node (ref "SW4") (pin "4") (pinfunction "4_4") (pintype "unspecified"))
      (node (ref "U1") (pin "2") (pinfunction "GND_2") (pintype "unspecified"))
      (node (ref "U1") (pin "4") (pinfunction "GND_4") (pintype "unspecified"))
      (node (ref "U10") (pin "3") (pinfunction "VSS_3") (pintype "unspecified"))
      (node (ref "U10") (pin "5") (pinfunction "SDO_5") (pintype "unspecified"))
      (node (ref "U10") (pin "8") (pinfunction "VSS_8") (pintype "unspecified"))
      (node (ref "U10") (pin "9") (pinfunction "VSS_9") (pintype "unspecified"))
      (node (ref "U11") (pin "1") (pinfunction "ADJ/GND_1") (pintype "unspecified"))
      (node (ref "U12") (pin "13") (pinfunction "PGND_13") (pintype "unspecified"))
      (node (ref "U12") (pin "6") (pinfunction "AGND_6") (pintype "unspecified"))
      (node (ref "U14") (pin "10") (pinfunction "VSS_10") (pintype "unspecified"))
      (node (ref "U14") (pin "19") (pinfunction "VSSA_19") (pintype "unspecified"))
      (node (ref "U14") (pin "26") (pinfunction "VSS_26") (pintype "unspecified"))
      (node (ref "U14") (pin "49") (pinfunction "VSS_49") (pintype "unspecified"))
      (node (ref "U14") (pin "74") (pinfunction "VSS_74") (pintype "unspecified"))
      (node (ref "U14") (pin "99") (pinfunction "VSS_99") (pintype "unspecified"))
      (node (ref "U15") (pin "1") (pinfunction "GND_1") (pintype "passive"))
      (node (ref "U15") (pin "40") (pinfunction "GND_40") (pintype "passive"))
      (node (ref "U15") (pin "41") (pinfunction "GND_41") (pintype "passive"))
      (node (ref "U16") (pin "1") (pinfunction "ADJ/GND_1") (pintype "unspecified"))
      (node (ref "U2") (pin "1") (pinfunction "GND_1") (pintype "unspecified"))
      (node (ref "U2") (pin "3") (pinfunction "GND_3") (pintype "unspecified"))
      (node (ref "U2") (pin "4") (pinfunction "GND_4") (pintype "unspecified"))
      (node (ref "U2") (pin "6") (pinfunction "GND_6") (pintype "unspecified"))
      (node (ref "U3") (pin "2") (pinfunction "GND_2") (pintype "unspecified"))
      (node (ref "U3") (pin "4") (pinfunction "GND_4") (pintype "unspecified"))
      (node (ref "U4") (pin "1") (pinfunction "GND_1") (pintype "unspecified"))
      (node (ref "U4") (pin "3") (pinfunction "GND_3") (pintype "unspecified"))
      (node (ref "U4") (pin "4") (pinfunction "GND_4") (pintype "unspecified"))
      (node (ref "U4") (pin "6") (pinfunction "GND_6") (pintype "unspecified"))
      (node (ref "U5") (pin "5") (pinfunction "VSS_5") (pintype "unspecified"))
      (node (ref "U6") (pin "5") (pinfunction "PWDN_5") (pintype "unspecified"))
      (node (ref "U6") (pin "6") (pinfunction "COMM_6") (pintype "unspecified"))
      (node (ref "U7") (pin "2") (pinfunction "2_2") (pintype "unspecified"))
      (node (ref "U7") (pin "3") (pinfunction "3_3") (pintype "unspecified"))
      (node (ref "U8") (pin "2") (pinfunction "2_2") (pintype "unspecified"))
      (node (ref "U8") (pin "3") (pinfunction "3_3") (pintype "unspecified"))
      (node (ref "U9") (pin "1") (pinfunction "GND_1") (pintype "unspecified"))
      (node (ref "U9") (pin "10") (pinfunction "GND_10") (pintype "unspecified"))
      (node (ref "U9") (pin "12") (pinfunction "GND_12") (pintype "unspecified"))
      (node (ref "USB1") (pin "1") (pinfunction "SHELL_1") (pintype "unspecified"))
      (node (ref "USB1") (pin "2") (pinfunction "SHELL_2") (pintype "unspecified"))
      (node (ref "USB1") (pin "3") (pinfunction "SHELL_3") (pintype "unspecified"))
      (node (ref "USB1") (pin "4") (pinfunction "SHELL_4") (pintype "unspecified"))
      (node (ref "USB1") (pin "A1B12") (pinfunction "GND_A1B12") (pintype "unspecified"))
      (node (ref "USB1") (pin "B1A12") (pinfunction "GND_B1A12") (pintype "unspecified"))
      (node (ref "X1") (pin "2") (pinfunction "GND_2") (pintype "input"))
      (node (ref "X1") (pin "4") (pinfunction "GND_4") (pintype "input"))
    )
    (net (code "13") (name "MCU3.3") (class "Default")
      (node (ref "C29") (pin "1") (pinfunction "1_1") (pintype "unspecified"))
      (node (ref "C30") (pin "1") (pinfunction "1_1") (pintype "unspecified"))
      (node (ref "C32") (pin "2") (pinfunction "2_2") (pintype "unspecified"))
      (node (ref "C33") (pin "2") (pinfunction "2_2") (pintype "unspecified"))
      (node (ref "C37") (pin "2") (pinfunction "2_2") (pintype "unspecified"))
      (node (ref "C39") (pin "2") (pinfunction "2_2") (pintype "unspecified"))
      (node (ref "C40") (pin "1") (pinfunction "1_1") (pintype "unspecified"))
      (node (ref "C41") (pin "1") (pinfunction "1_1") (pintype "unspecified"))
      (node (ref "C42") (pin "1") (pinfunction "1_1") (pintype "unspecified"))
      (node (ref "C44") (pin "2") (pinfunction "2_2") (pintype "unspecified"))
      (node (ref "C48") (pin "2") (pinfunction "2_2") (pintype "unspecified"))
      (node (ref "C53") (pin "2") (pinfunction "2_2") (pintype "input"))
      (node (ref "DE1") (pin "1") (pinfunction "1_1") (pintype "unspecified"))
      (node (ref "J1") (pin "1") (pinfunction "1_1") (pintype "unspecified"))
      (node (ref "R32") (pin "1") (pinfunction "1_1") (pintype "input"))
      (node (ref "R36") (pin "1") (pinfunction "1_1") (pintype "unspecified"))
      (node (ref "R38") (pin "1") (pinfunction "1_1") (pintype "unspecified"))
      (node (ref "SW3") (pin "4") (pinfunction "4_4") (pintype "unspecified"))
      (node (ref "U11") (pin "2") (pinfunction "Vout_2") (pintype "unspecified"))
      (node (ref "U11") (pin "4") (pinfunction "Vout_4") (pintype "unspecified"))
      (node (ref "U14") (pin "100") (pinfunction "VDD_100") (pintype "unspecified"))
      (node (ref "U14") (pin "11") (pinfunction "VDD_11") (pintype "unspecified"))
      (node (ref "U14") (pin "20") (pinfunction "VREF+_20") (pintype "unspecified"))
      (node (ref "U14") (pin "21") (pinfunction "VDDA_21") (pintype "unspecified"))
      (node (ref "U14") (pin "27") (pinfunction "VDD_27") (pintype "unspecified"))
      (node (ref "U14") (pin "50") (pinfunction "VDD_50") (pintype "unspecified"))
      (node (ref "U14") (pin "6") (pinfunction "VBAT_6") (pintype "unspecified"))
      (node (ref "U14") (pin "75") (pinfunction "VDD_75") (pintype "unspecified"))
    )
    (net (code "14") (name "MID") (class "Default")
      (node (ref "BT1") (pin "1") (pinfunction "1_1") (pintype "input"))
      (node (ref "BT2") (pin "2") (pinfunction "2_2") (pintype "input"))
      (node (ref "U12") (pin "9") (pinfunction "MID_9") (pintype "unspecified"))
    )
    (net (code "15") (name "MOUT") (class "Default")
      (node (ref "DE8") (pin "1") (pinfunction "1_1") (pintype "unspecified"))
      (node (ref "R2") (pin "1") (pinfunction "1_1") (pintype "input"))
      (node (ref "R27") (pin "1") (pinfunction "1_1") (pintype "input"))
      (node (ref "U5") (pin "1") (pinfunction "OUT_1") (pintype "unspecified"))
    )
    (net (code "16") (name "MP") (class "Default")
      (node (ref "C38") (pin "1") (pinfunction "1_1") (pintype "unspecified"))
      (node (ref "R24") (pin "1") (pinfunction "1_1") (pintype "input"))
      (node (ref "U12") (pin "4") (pinfunction "VCC_4") (pintype "unspecified"))
    )
    (net (code "17") (name "NRST") (class "Default")
      (node (ref "C49") (pin "1") (pinfunction "1_1") (pintype "input"))
      (node (ref "C50") (pin "2") (pinfunction "2_2") (pintype "unspecified"))
      (node (ref "J1") (pin "5") (pinfunction "5_5") (pintype "unspecified"))
      (node (ref "R32") (pin "2") (pinfunction "2_2") (pintype "input"))
      (node (ref "SW1") (pin "1") (pinfunction "1_1") (pintype "unspecified"))
      (node (ref "U14") (pin "14") (pinfunction "NRST_14") (pintype "unspecified"))
      (node (ref "U15") (pin "6") (pinfunction "IO6_6") (pintype "unspecified"))
    )
    (net (code "18") (name "Net-(C2-Pad2)") (class "Default")
      (node (ref "C2") (pin "2") (pinfunction "2_2") (pintype "input"))
      (node (ref "R1") (pin "1") (pinfunction "1_1") (pintype "input"))
      (node (ref "U6") (pin "1") (pinfunction "VPOS_1") (pintype "unspecified"))
    )
    (net (code "19") (name "Net-(C11-Pad1)") (class "Default")
      (node (ref "C11") (pin "1") (pinfunction "1_1") (pintype "input"))
      (node (ref "R9") (pin "2") (pinfunction "2_2") (pintype "input"))
      (node (ref "U6") (pin "4") (pinfunction "VPOS_4") (pintype "unspecified"))
    )
    (net (code "20") (name "Net-(C12-Pad2)") (class "Default")
      (node (ref "C12") (pin "2") (pinfunction "2_2") (pintype "unspecified"))
      (node (ref "R6") (pin "1") (pinfunction "1_1") (pintype "input"))
    )
    (net (code "21") (name "Net-(C15-Pad2)") (class "Default")
      (node (ref "C15") (pin "2") (pinfunction "2_2") (pintype "unspecified"))
      (node (ref "R7") (pin "1") (pinfunction "1_1") (pintype "input"))
    )
    (net (code "22") (name "Net-(C18-Pad2)") (class "Default")
      (node (ref "C18") (pin "2") (pinfunction "2_2") (pintype "input"))
      (node (ref "R8") (pin "1") (pinfunction "1_1") (pintype "input"))
    )
    (net (code "23") (name "Net-(C19-Pad2)") (class "Default")
      (node (ref "C19") (pin "2") (pinfunction "2_2") (pintype "input"))
      (node (ref "R10") (pin "1") (pinfunction "1_1") (pintype "input"))
      (node (ref "R11") (pin "2") (pinfunction "2_2") (pintype "input"))
    )
    (net (code "24") (name "Net-(C43-Pad2)") (class "Default")
      (node (ref "C43") (pin "2") (pinfunction "2_2") (pintype "input"))
      (node (ref "U14") (pin "73") (pinfunction "VCAP_73") (pintype "unspecified"))
    )
    (net (code "25") (name "Net-(C47-Pad2)") (class "Default")
      (node (ref "C47") (pin "2") (pinfunction "2_2") (pintype "input"))
      (node (ref "U14") (pin "48") (pinfunction "VCAP_48") (pintype "unspecified"))
    )
    (net (code "26") (name "Net-(D1-A)") (class "Default")
      (node (ref "C4") (pin "1") (pinfunction "1_1") (pintype "unspecified"))
      (node (ref "D1") (pin "2") (pinfunction "A_2") (pintype "unspecified"))
      (node (ref "RF1") (pin "5") (pinfunction "IN_5") (pintype "unspecified"))
    )
    (net (code "27") (name "Net-(JP1-SIG)") (class "Default")
      (node (ref "JP1") (pin "1") (pinfunction "SIG_1") (pintype "unspecified"))
      (node (ref "L4") (pin "2") (pinfunction "2_2") (pintype "unspecified"))
      (node (ref "U9") (pin "11") (pinfunction "RF_IN_11") (pintype "unspecified"))
    )
    (net (code "28") (name "Net-(L1-Pad2)") (class "Default")
      (node (ref "L1") (pin "2") (pinfunction "2_2") (pintype "unspecified"))
      (node (ref "R6") (pin "2") (pinfunction "2_2") (pintype "input"))
    )
    (net (code "29") (name "Net-(L2-Pad2)") (class "Default")
      (node (ref "L2") (pin "2") (pinfunction "2_2") (pintype "unspecified"))
      (node (ref "R7") (pin "2") (pinfunction "2_2") (pintype "input"))
    )
    (net (code "30") (name "Net-(L4-Pad1)") (class "Default")
      (node (ref "L4") (pin "1") (pinfunction "1_1") (pintype "unspecified"))
      (node (ref "R17") (pin "1") (pinfunction "1_1") (pintype "input"))
    )
    (net (code "31") (name "Net-(LED1-A)") (class "Default")
      (node (ref "LED1") (pin "2") (pinfunction "A_2") (pintype "input"))
      (node (ref "R13") (pin "1") (pinfunction "1_1") (pintype "input"))
    )
    (net (code "32") (name "Net-(LED2-A)") (class "Default")
      (node (ref "LED2") (pin "2") (pinfunction "A_2") (pintype "input"))
      (node (ref "R14") (pin "1") (pinfunction "1_1") (pintype "input"))
    )
    (net (code "33") (name "Net-(LED3-A)") (class "Default")
      (node (ref "LED3") (pin "2") (pinfunction "A_2") (pintype "input"))
      (node (ref "R15") (pin "1") (pinfunction "1_1") (pintype "input"))
    )
    (net (code "34") (name "Net-(LED4-A)") (class "Default")
      (node (ref "LED4") (pin "2") (pinfunction "A_2") (pintype "input"))
      (node (ref "R18") (pin "1") (pinfunction "1_1") (pintype "input"))
    )
    (net (code "35") (name "Net-(LED5-+)") (class "Default")
      (node (ref "LED5") (pin "1") (pinfunction "+_1") (pintype "unspecified"))
      (node (ref "R33") (pin "1") (pinfunction "1_1") (pintype "input"))
    )
    (net (code "36") (name "Net-(U1-IN)") (class "Default")
      (node (ref "C4") (pin "2") (pinfunction "2_2") (pintype "unspecified"))
      (node (ref "L1") (pin "1") (pinfunction "1_1") (pintype "unspecified"))
      (node (ref "U1") (pin "1") (pinfunction "IN_1") (pintype "unspecified"))
    )
    (net (code "37") (name "Net-(U1-OUT)") (class "Default")
      (node (ref "C5") (pin "1") (pinfunction "1_1") (pintype "unspecified"))
      (node (ref "U1") (pin "3") (pinfunction "OUT_3") (pintype "unspecified"))
      (node (ref "U7") (pin "1") (pinfunction "1_1") (pintype "unspecified"))
    )
    (net (code "38") (name "Net-(U2-INPUT)") (class "Default")
      (node (ref "C5") (pin "2") (pinfunction "2_2") (pintype "unspecified"))
      (node (ref "U2") (pin "2") (pinfunction "INPUT_2") (pintype "unspecified"))
    )
    (net (code "39") (name "Net-(U2-OUTPUT)") (class "Default")
      (node (ref "C6") (pin "1") (pinfunction "1_1") (pintype "unspecified"))
      (node (ref "U2") (pin "5") (pinfunction "OUTPUT_5") (pintype "unspecified"))
    )
    (net (code "40") (name "Net-(U3-IN)") (class "Default")
      (node (ref "C6") (pin "2") (pinfunction "2_2") (pintype "unspecified"))
      (node (ref "L2") (pin "1") (pinfunction "1_1") (pintype "unspecified"))
      (node (ref "U3") (pin "1") (pinfunction "IN_1") (pintype "unspecified"))
    )
    (net (code "41") (name "Net-(U3-OUT)") (class "Default")
      (node (ref "C7") (pin "1") (pinfunction "1_1") (pintype "unspecified"))
      (node (ref "U3") (pin "3") (pinfunction "OUT_3") (pintype "unspecified"))
      (node (ref "U8") (pin "1") (pinfunction "1_1") (pintype "unspecified"))
    )
    (net (code "42") (name "Net-(U4-INPUT)") (class "Default")
      (node (ref "C7") (pin "2") (pinfunction "2_2") (pintype "unspecified"))
      (node (ref "U4") (pin "2") (pinfunction "INPUT_2") (pintype "unspecified"))
    )
    (net (code "43") (name "Net-(U4-OUTPUT)") (class "Default")
      (node (ref "C8") (pin "1") (pinfunction "1_1") (pintype "unspecified"))
      (node (ref "U4") (pin "5") (pinfunction "OUTPUT_5") (pintype "unspecified"))
    )
    (net (code "44") (name "Net-(U5-+IN)") (class "Default")
      (node (ref "C3") (pin "1") (pinfunction "1_1") (pintype "unspecified"))
      (node (ref "R4") (pin "1") (pinfunction "1_1") (pintype "input"))
      (node (ref "U5") (pin "3") (pinfunction "+IN_3") (pintype "unspecified"))
    )
    (net (code "45") (name "Net-(U6-INHI)") (class "Default")
      (node (ref "C8") (pin "2") (pinfunction "2_2") (pintype "unspecified"))
      (node (ref "L3") (pin "2") (pinfunction "2_2") (pintype "unspecified"))
      (node (ref "U6") (pin "2") (pinfunction "INHI_2") (pintype "unspecified"))
    )
    (net (code "46") (name "Net-(U6-INLO)") (class "Default")
      (node (ref "C9") (pin "2") (pinfunction "2_2") (pintype "unspecified"))
      (node (ref "L3") (pin "1") (pinfunction "1_1") (pintype "unspecified"))
      (node (ref "U6") (pin "3") (pinfunction "INLO_3") (pintype "unspecified"))
    )
    (net (code "47") (name "Net-(U6-VOUT)") (class "Default")
      (node (ref "R3") (pin "1") (pinfunction "1_1") (pintype "input"))
      (node (ref "R4") (pin "2") (pinfunction "2_2") (pintype "input"))
      (node (ref "R5") (pin "1") (pinfunction "1_1") (pintype "input"))
      (node (ref "R8") (pin "2") (pinfunction "2_2") (pintype "input"))
      (node (ref "U6") (pin "7") (pinfunction "VSET_7") (pintype "unspecified"))
      (node (ref "U6") (pin "8") (pinfunction "VOUT_8") (pintype "unspecified"))
    )
    (net (code "48") (name "Net-(U9-RESET_N)") (class "Default")
      (node (ref "R16") (pin "1") (pinfunction "1_1") (pintype "input"))
      (node (ref "U9") (pin "9") (pinfunction "RESET_N_9") (pintype "unspecified"))
    )
    (net (code "49") (name "Net-(U9-SAFEBOOT_N)") (class "Default")
      (node (ref "R12") (pin "2") (pinfunction "2_2") (pintype "input"))
      (node (ref "U9") (pin "18") (pinfunction "SAFEBOOT_N_18") (pintype "unspecified"))
    )
    (net (code "50") (name "Net-(U12-BST)") (class "Default")
      (node (ref "C31") (pin "2") (pinfunction "2_2") (pintype "unspecified"))
      (node (ref "U12") (pin "3") (pinfunction "BST_3") (pintype "unspecified"))
    )
    (net (code "51") (name "Net-(U12-CV)") (class "Default")
      (node (ref "R19") (pin "1") (pinfunction "1_1") (pintype "input"))
      (node (ref "U12") (pin "17") (pinfunction "CV_17") (pintype "unspecified"))
    )
    (net (code "52") (name "Net-(U12-ISET)") (class "Default")
      (node (ref "R20") (pin "2") (pinfunction "2_2") (pintype "input"))
      (node (ref "U12") (pin "5") (pinfunction "ISET_5") (pintype "unspecified"))
    )
    (net (code "53") (name "Net-(U12-NTC)") (class "Default")
      (node (ref "R23") (pin "2") (pinfunction "2_2") (pintype "input"))
      (node (ref "R24") (pin "2") (pinfunction "2_2") (pintype "input"))
      (node (ref "U12") (pin "8") (pinfunction "NTC_8") (pintype "unspecified"))
    )
    (net (code "54") (name "Net-(U12-VLIM)") (class "Default")
      (node (ref "R21") (pin "2") (pinfunction "2_2") (pintype "input"))
      (node (ref "R22") (pin "2") (pinfunction "2_2") (pintype "input"))
      (node (ref "U12") (pin "7") (pinfunction "VLIM_7") (pintype "unspecified"))
    )
    (net (code "55") (name "Net-(U14-PA5)") (class "Default")
      (node (ref "R27") (pin "2") (pinfunction "2_2") (pintype "input"))
      (node (ref "U14") (pin "29") (pinfunction "PA5_29") (pintype "unspecified"))
    )
    (net (code "56") (name "Net-(U14-PA8)") (class "Default")
      (node (ref "R28") (pin "2") (pinfunction "2_2") (pintype "input"))
      (node (ref "U14") (pin "67") (pinfunction "PA8_67") (pintype "unspecified"))
    )
    (net (code "57") (name "Net-(U14-PH1-OSC_OUT)") (class "Default")
      (node (ref "R26") (pin "2") (pinfunction "2_2") (pintype "input"))
      (node (ref "U14") (pin "13") (pinfunction "PH1-OSC_OUT_13") (pintype "unspecified"))
    )
    (net (code "58") (name "OP3.3") (class "Default")
      (node (ref "C1") (pin "1") (pinfunction "1_1") (pintype "input"))
      (node (ref "C13") (pin "2") (pinfunction "2_2") (pintype "unspecified"))
      (node (ref "C14") (pin "2") (pinfunction "2_2") (pintype "unspecified"))
      (node (ref "C16") (pin "2") (pinfunction "2_2") (pintype "unspecified"))
      (node (ref "C17") (pin "2") (pinfunction "2_2") (pintype "unspecified"))
      (node (ref "C20") (pin "1") (pinfunction "1_1") (pintype "input"))
      (node (ref "C21") (pin "2") (pinfunction "2_2") (pintype "input"))
      (node (ref "C23") (pin "1") (pinfunction "1_1") (pintype "input"))
      (node (ref "C24") (pin "2") (pinfunction "2_2") (pintype "input"))
      (node (ref "C25") (pin "1") (pinfunction "1_1") (pintype "input"))
      (node (ref "C26") (pin "1") (pinfunction "1_1") (pintype "input"))
      (node (ref "C46") (pin "1") (pinfunction "1_1") (pintype "input"))
      (node (ref "C51") (pin "2") (pinfunction "2_2") (pintype "input"))
      (node (ref "DE2") (pin "1") (pinfunction "1_1") (pintype "unspecified"))
      (node (ref "R1") (pin "2") (pinfunction "2_2") (pintype "input"))
      (node (ref "R12") (pin "1") (pinfunction "1_1") (pintype "input"))
      (node (ref "R16") (pin "2") (pinfunction "2_2") (pintype "input"))
      (node (ref "R2") (pin "2") (pinfunction "2_2") (pintype "input"))
      (node (ref "R29") (pin "2") (pinfunction "2_2") (pintype "input"))
      (node (ref "R3") (pin "2") (pinfunction "2_2") (pintype "input"))
      (node (ref "R33") (pin "2") (pinfunction "2_2") (pintype "input"))
      (node (ref "R34") (pin "1") (pinfunction "1_1") (pintype "input"))
      (node (ref "R37") (pin "1") (pinfunction "1_1") (pintype "input"))
      (node (ref "R9") (pin "1") (pinfunction "1_1") (pintype "input"))
      (node (ref "U10") (pin "1") (pinfunction "VDDIO_1") (pintype "unspecified"))
      (node (ref "U10") (pin "10") (pinfunction "VDD_10") (pintype "unspecified"))
      (node (ref "U10") (pin "6") (pinfunction "CSB_6") (pintype "unspecified"))
      (node (ref "U15") (pin "2") (pinfunction "3V3_2") (pintype "passive"))
      (node (ref "U16") (pin "2") (pinfunction "Vout_2") (pintype "unspecified"))
      (node (ref "U16") (pin "4") (pinfunction "Vout_4") (pintype "unspecified"))
      (node (ref "U5") (pin "2") (pinfunction "VDD_2") (pintype "unspecified"))
      (node (ref "U7") (pin "4") (pinfunction "4_4") (pintype "unspecified"))
      (node (ref "U8") (pin "4") (pinfunction "4_4") (pintype "unspecified"))
      (node (ref "U9") (pin "6") (pinfunction "V_BCKP_6") (pintype "unspecified"))
      (node (ref "U9") (pin "7") (pinfunction "V_IO_7") (pintype "unspecified"))
      (node (ref "U9") (pin "8") (pinfunction "VCC_8") (pintype "unspecified"))
    )
    (net (code "59") (name "PWM") (class "Default")
      (node (ref "DE10") (pin "1") (pinfunction "1_1") (pintype "unspecified"))
      (node (ref "R11") (pin "1") (pinfunction "1_1") (pintype "input"))
      (node (ref "R28") (pin "1") (pinfunction "1_1") (pintype "input"))
    )
    (net (code "60") (name "RF") (class "Default")
      (node (ref "C22") (pin "1") (pinfunction "1_1") (pintype "unspecified"))
      (node (ref "R17") (pin "2") (pinfunction "2_2") (pintype "input"))
      (node (ref "U9") (pin "14") (pinfunction "VCC_RF_14") (pintype "unspecified"))
    )
    (net (code "61") (name "RX") (class "Default")
      (node (ref "U14") (pin "86") (pinfunction "PD5_86") (pintype "unspecified"))
      (node (ref "U9") (pin "3") (pinfunction "RXD_3") (pintype "unspecified"))
    )
    (net (code "62") (name "RXTX") (class "Default")
      (node (ref "U14") (pin "69") (pinfunction "PA10_69") (pintype "unspecified"))
      (node (ref "U15") (pin "37") (pinfunction "TXD0_37") (pintype "unspecified"))
    )
    (net (code "63") (name "SCL") (class "Default")
      (node (ref "R36") (pin "2") (pinfunction "2_2") (pintype "unspecified"))
      (node (ref "U10") (pin "2") (pinfunction "SCK_2") (pintype "unspecified"))
      (node (ref "U12") (pin "14") (pinfunction "SCL_14") (pintype "unspecified"))
      (node (ref "U14") (pin "92") (pinfunction "PB6_92") (pintype "unspecified"))
    )
    (net (code "64") (name "SDA") (class "Default")
      (node (ref "R38") (pin "2") (pinfunction "2_2") (pintype "unspecified"))
      (node (ref "U10") (pin "4") (pinfunction "SDI_4") (pintype "unspecified"))
      (node (ref "U12") (pin "15") (pinfunction "SDA_15") (pintype "unspecified"))
      (node (ref "U14") (pin "93") (pinfunction "PB7_93") (pintype "unspecified"))
    )
    (net (code "65") (name "ST1") (class "Default")
      (node (ref "R15") (pin "2") (pinfunction "2_2") (pintype "input"))
      (node (ref "U15") (pin "8") (pinfunction "IO15_8") (pintype "unspecified"))
    )
    (net (code "66") (name "ST2") (class "Default")
      (node (ref "R14") (pin "2") (pinfunction "2_2") (pintype "input"))
      (node (ref "U15") (pin "9") (pinfunction "IO16_9") (pintype "unspecified"))
    )
    (net (code "67") (name "ST3") (class "Default")
      (node (ref "R13") (pin "2") (pinfunction "2_2") (pintype "input"))
      (node (ref "U15") (pin "10") (pinfunction "IO17_10") (pintype "unspecified"))
    )
    (net (code "68") (name "STAT") (class "Default")
      (node (ref "LED4") (pin "1") (pinfunction "C_1") (pintype "input"))
      (node (ref "U12") (pin "16") (pinfunction "STAT#_16") (pintype "unspecified"))
    )
    (net (code "69") (name "STBOOT") (class "Default")
      (node (ref "C53") (pin "1") (pinfunction "1_1") (pintype "input"))
      (node (ref "R25") (pin "2") (pinfunction "2_2") (pintype "input"))
      (node (ref "R35") (pin "2") (pinfunction "2_2") (pintype "input"))
      (node (ref "SW3") (pin "1") (pinfunction "1_1") (pintype "unspecified"))
      (node (ref "U14") (pin "94") (pinfunction "BOOT0_94") (pintype "unspecified"))
    )
    (net (code "70") (name "SW") (class "Default")
      (node (ref "C31") (pin "1") (pinfunction "1_1") (pintype "unspecified"))
      (node (ref "L5") (pin "1") (pinfunction "1_1") (pintype "unspecified"))
      (node (ref "U12") (pin "12") (pinfunction "SW_12") (pintype "unspecified"))
      (node (ref "U12") (pin "2") (pinfunction "SW_2") (pintype "unspecified"))
    )
    (net (code "71") (name "SWCLK") (class "Default")
      (node (ref "J1") (pin "4") (pinfunction "4_4") (pintype "unspecified"))
      (node (ref "U14") (pin "76") (pinfunction "PA14_76") (pintype "unspecified"))
    )
    (net (code "72") (name "SWDIO") (class "Default")
      (node (ref "J1") (pin "6") (pinfunction "6_6") (pintype "unspecified"))
      (node (ref "U14") (pin "72") (pinfunction "PA13_72") (pintype "unspecified"))
    )
    (net (code "73") (name "SWO") (class "Default")
      (node (ref "J1") (pin "2") (pinfunction "2_2") (pintype "unspecified"))
      (node (ref "U14") (pin "89") (pinfunction "PB3_89") (pintype "unspecified"))
    )
    (net (code "74") (name "SYS") (class "Default")
      (node (ref "C35") (pin "2") (pinfunction "2_2") (pintype "input"))
      (node (ref "C36") (pin "2") (pinfunction "2_2") (pintype "input"))
      (node (ref "DE3") (pin "1") (pinfunction "1_1") (pintype "unspecified"))
      (node (ref "U12") (pin "11") (pinfunction "SYS_11") (pintype "unspecified"))
      (node (ref "U13") (pin "1") (pinfunction "1_1") (pintype "unspecified"))
    )
    (net (code "75") (name "SYS2") (class "Default")
      (node (ref "DE4") (pin "1") (pinfunction "1_1") (pintype "unspecified"))
      (node (ref "U11") (pin "3") (pinfunction "Vin_3") (pintype "passive"))
      (node (ref "U13") (pin "2") (pinfunction "2_2") (pintype "unspecified"))
      (node (ref "U16") (pin "3") (pinfunction "Vin_3") (pintype "passive"))
    )
    (net (code "76") (name "TP") (class "Default")
      (node (ref "U14") (pin "22") (pinfunction "PA0_22") (pintype "unspecified"))
      (node (ref "U9") (pin "4") (pinfunction "TIMEPULSE_4") (pintype "unspecified"))
    )
    (net (code "77") (name "TX") (class "Default")
      (node (ref "U14") (pin "87") (pinfunction "PD6_87") (pintype "unspecified"))
      (node (ref "U9") (pin "2") (pinfunction "TXD_2") (pintype "unspecified"))
    )
    (net (code "78") (name "TXRX") (class "Default")
      (node (ref "U14") (pin "68") (pinfunction "PA9_68") (pintype "unspecified"))
      (node (ref "U15") (pin "36") (pinfunction "RXD0_36") (pintype "unspecified"))
    )
    (net (code "79") (name "USB") (class "Default")
      (node (ref "C45") (pin "2") (pinfunction "2_2") (pintype "input"))
      (node (ref "D2") (pin "2") (pinfunction "2_2") (pintype "unspecified"))
      (node (ref "DE6") (pin "1") (pinfunction "1_1") (pintype "unspecified"))
      (node (ref "R18") (pin "2") (pinfunction "2_2") (pintype "input"))
      (node (ref "USB1") (pin "A4B9") (pinfunction "VBUS_A4B9") (pintype "unspecified"))
      (node (ref "USB1") (pin "B4A9") (pinfunction "VBUS_B4A9") (pintype "unspecified"))
    )
    (net (code "80") (name "XIN") (class "Default")
      (node (ref "C56") (pin "2") (pinfunction "2_2") (pintype "input"))
      (node (ref "U14") (pin "12") (pinfunction "PH0-OSC_IN_12") (pintype "unspecified"))
      (node (ref "X1") (pin "1") (pinfunction "1_1") (pintype "input"))
    )
    (net (code "81") (name "XOUT") (class "Default")
      (node (ref "C54") (pin "1") (pinfunction "1_1") (pintype "input"))
      (node (ref "R26") (pin "1") (pinfunction "1_1") (pintype "input"))
      (node (ref "X1") (pin "3") (pinfunction "3_3") (pintype "input"))
    )
    (net (code "82") (name "unconnected-(SW1-Pad2)") (class "Default")
      (node (ref "SW1") (pin "2") (pinfunction "2_2") (pintype "unspecified+no_connect"))
    )
    (net (code "83") (name "unconnected-(SW1-Pad3)") (class "Default")
      (node (ref "SW1") (pin "3") (pinfunction "3_3") (pintype "unspecified+no_connect"))
    )
    (net (code "84") (name "unconnected-(SW2-Pad2)") (class "Default")
      (node (ref "SW2") (pin "2") (pinfunction "2_2") (pintype "unspecified+no_connect"))
    )
    (net (code "85") (name "unconnected-(SW2-Pad3)") (class "Default")
      (node (ref "SW2") (pin "3") (pinfunction "3_3") (pintype "unspecified+no_connect"))
    )
    (net (code "86") (name "unconnected-(SW3-Pad2)") (class "Default")
      (node (ref "SW3") (pin "2") (pinfunction "2_2") (pintype "unspecified+no_connect"))
    )
    (net (code "87") (name "unconnected-(SW3-Pad3)") (class "Default")
      (node (ref "SW3") (pin "3") (pinfunction "3_3") (pintype "unspecified+no_connect"))
    )
    (net (code "88") (name "unconnected-(SW4-Pad2)") (class "Default")
      (node (ref "SW4") (pin "2") (pinfunction "2_2") (pintype "unspecified+no_connect"))
    )
    (net (code "89") (name "unconnected-(SW4-Pad3)") (class "Default")
      (node (ref "SW4") (pin "3") (pinfunction "3_3") (pintype "unspecified+no_connect"))
    )
    (net (code "90") (name "unconnected-(U9-EXTINT-Pad5)") (class "Default")
      (node (ref "U9") (pin "5") (pinfunction "EXTINT_5") (pintype "unspecified+no_connect"))
    )
    (net (code "91") (name "unconnected-(U9-LNA_EN-Pad13)") (class "Default")
      (node (ref "U9") (pin "13") (pinfunction "LNA_EN_13") (pintype "unspecified+no_connect"))
    )
    (net (code "92") (name "unconnected-(U9-SCL-Pad17)") (class "Default")
      (node (ref "U9") (pin "17") (pinfunction "SCL_17") (pintype "unspecified+no_connect"))
    )
    (net (code "93") (name "unconnected-(U9-SDA-Pad16)") (class "Default")
      (node (ref "U9") (pin "16") (pinfunction "SDA_16") (pintype "unspecified+no_connect"))
    )
    (net (code "94") (name "unconnected-(U9-VIO_SEL-Pad15)") (class "Default")
      (node (ref "U9") (pin "15") (pinfunction "VIO_SEL_15") (pintype "unspecified+no_connect"))
    )
    (net (code "95") (name "unconnected-(U10-INT-Pad7)") (class "Default")
      (node (ref "U10") (pin "7") (pinfunction "INT_7") (pintype "unspecified+no_connect"))
    )
    (net (code "96") (name "unconnected-(U13-Pad3)") (class "Default")
      (node (ref "U13") (pin "3") (pinfunction "3_3") (pintype "unspecified+no_connect"))
    )
    (net (code "97") (name "unconnected-(U14-PA1-Pad23)") (class "Default")
      (node (ref "U14") (pin "23") (pinfunction "PA1_23") (pintype "unspecified+no_connect"))
    )
    (net (code "98") (name "unconnected-(U14-PA2-Pad24)") (class "Default")
      (node (ref "U14") (pin "24") (pinfunction "PA2_24") (pintype "unspecified+no_connect"))
    )
    (net (code "99") (name "unconnected-(U14-PA4-Pad28)") (class "Default")
      (node (ref "U14") (pin "28") (pinfunction "PA4_28") (pintype "unspecified+no_connect"))
    )
    (net (code "100") (name "unconnected-(U14-PA6-Pad30)") (class "Default")
      (node (ref "U14") (pin "30") (pinfunction "PA6_30") (pintype "unspecified+no_connect"))
    )
    (net (code "101") (name "unconnected-(U14-PA7-Pad31)") (class "Default")
      (node (ref "U14") (pin "31") (pinfunction "PA7_31") (pintype "unspecified+no_connect"))
    )
    (net (code "102") (name "unconnected-(U14-PA11-Pad70)") (class "Default")
      (node (ref "U14") (pin "70") (pinfunction "PA11_70") (pintype "unspecified+no_connect"))
    )
    (net (code "103") (name "unconnected-(U14-PA12-Pad71)") (class "Default")
      (node (ref "U14") (pin "71") (pinfunction "PA12_71") (pintype "unspecified+no_connect"))
    )
    (net (code "104") (name "unconnected-(U14-PA15-Pad77)") (class "Default")
      (node (ref "U14") (pin "77") (pinfunction "PA15_77") (pintype "unspecified+no_connect"))
    )
    (net (code "105") (name "unconnected-(U14-PB1-Pad35)") (class "Default")
      (node (ref "U14") (pin "35") (pinfunction "PB1_35") (pintype "unspecified+no_connect"))
    )
    (net (code "106") (name "unconnected-(U14-PB2-Pad36)") (class "Default")
      (node (ref "U14") (pin "36") (pinfunction "PB2_36") (pintype "unspecified+no_connect"))
    )
    (net (code "107") (name "unconnected-(U14-PB4-Pad90)") (class "Default")
      (node (ref "U14") (pin "90") (pinfunction "PB4_90") (pintype "unspecified+no_connect"))
    )
    (net (code "108") (name "unconnected-(U14-PB5-Pad91)") (class "Default")
      (node (ref "U14") (pin "91") (pinfunction "PB5_91") (pintype "unspecified+no_connect"))
    )
    (net (code "109") (name "unconnected-(U14-PB8-Pad95)") (class "Default")
      (node (ref "U14") (pin "95") (pinfunction "PB8_95") (pintype "unspecified+no_connect"))
    )
    (net (code "110") (name "unconnected-(U14-PB9-Pad96)") (class "Default")
      (node (ref "U14") (pin "96") (pinfunction "PB9_96") (pintype "unspecified+no_connect"))
    )
    (net (code "111") (name "unconnected-(U14-PB10-Pad46)") (class "Default")
      (node (ref "U14") (pin "46") (pinfunction "PB10_46") (pintype "unspecified+no_connect"))
    )
    (net (code "112") (name "unconnected-(U14-PB11-Pad47)") (class "Default")
      (node (ref "U14") (pin "47") (pinfunction "PB11_47") (pintype "unspecified+no_connect"))
    )
    (net (code "113") (name "unconnected-(U14-PB12-Pad51)") (class "Default")
      (node (ref "U14") (pin "51") (pinfunction "PB12_51") (pintype "unspecified+no_connect"))
    )
    (net (code "114") (name "unconnected-(U14-PB13-Pad52)") (class "Default")
      (node (ref "U14") (pin "52") (pinfunction "PB13_52") (pintype "unspecified+no_connect"))
    )
    (net (code "115") (name "unconnected-(U14-PB14-Pad53)") (class "Default")
      (node (ref "U14") (pin "53") (pinfunction "PB14_53") (pintype "unspecified+no_connect"))
    )
    (net (code "116") (name "unconnected-(U14-PB15-Pad54)") (class "Default")
      (node (ref "U14") (pin "54") (pinfunction "PB15_54") (pintype "unspecified+no_connect"))
    )
    (net (code "117") (name "unconnected-(U14-PC0-Pad15)") (class "Default")
      (node (ref "U14") (pin "15") (pinfunction "PC0_15") (pintype "unspecified+no_connect"))
    )
    (net (code "118") (name "unconnected-(U14-PC1-Pad16)") (class "Default")
      (node (ref "U14") (pin "16") (pinfunction "PC1_16") (pintype "unspecified+no_connect"))
    )
    (net (code "119") (name "unconnected-(U14-PC2_C-Pad17)") (class "Default")
      (node (ref "U14") (pin "17") (pinfunction "PC2_C_17") (pintype "unspecified+no_connect"))
    )
    (net (code "120") (name "unconnected-(U14-PC3_C-Pad18)") (class "Default")
      (node (ref "U14") (pin "18") (pinfunction "PC3_C_18") (pintype "unspecified+no_connect"))
    )
    (net (code "121") (name "unconnected-(U14-PC4-Pad32)") (class "Default")
      (node (ref "U14") (pin "32") (pinfunction "PC4_32") (pintype "unspecified+no_connect"))
    )
    (net (code "122") (name "unconnected-(U14-PC5-Pad33)") (class "Default")
      (node (ref "U14") (pin "33") (pinfunction "PC5_33") (pintype "unspecified+no_connect"))
    )
    (net (code "123") (name "unconnected-(U14-PC6-Pad63)") (class "Default")
      (node (ref "U14") (pin "63") (pinfunction "PC6_63") (pintype "unspecified+no_connect"))
    )
    (net (code "124") (name "unconnected-(U14-PC7-Pad64)") (class "Default")
      (node (ref "U14") (pin "64") (pinfunction "PC7_64") (pintype "unspecified+no_connect"))
    )
    (net (code "125") (name "unconnected-(U14-PC8-Pad65)") (class "Default")
      (node (ref "U14") (pin "65") (pinfunction "PC8_65") (pintype "unspecified+no_connect"))
    )
    (net (code "126") (name "unconnected-(U14-PC9-Pad66)") (class "Default")
      (node (ref "U14") (pin "66") (pinfunction "PC9_66") (pintype "unspecified+no_connect"))
    )
    (net (code "127") (name "unconnected-(U14-PC10-Pad78)") (class "Default")
      (node (ref "U14") (pin "78") (pinfunction "PC10_78") (pintype "unspecified+no_connect"))
    )
    (net (code "128") (name "unconnected-(U14-PC11-Pad79)") (class "Default")
      (node (ref "U14") (pin "79") (pinfunction "PC11_79") (pintype "unspecified+no_connect"))
    )
    (net (code "129") (name "unconnected-(U14-PC12-Pad80)") (class "Default")
      (node (ref "U14") (pin "80") (pinfunction "PC12_80") (pintype "unspecified+no_connect"))
    )
    (net (code "130") (name "unconnected-(U14-PC13-Pad7)") (class "Default")
      (node (ref "U14") (pin "7") (pinfunction "PC13_7") (pintype "unspecified+no_connect"))
    )
    (net (code "131") (name "unconnected-(U14-PC14-OSC32_IN-Pad8)") (class "Default")
      (node (ref "U14") (pin "8") (pinfunction "PC14-OSC32_IN_8") (pintype "unspecified+no_connect"))
    )
    (net (code "132") (name "unconnected-(U14-PC15-OSC32_OUT-Pad9)") (class "Default")
      (node (ref "U14") (pin "9") (pinfunction "PC15-OSC32_OUT_9") (pintype "unspecified+no_connect"))
    )
    (net (code "133") (name "unconnected-(U14-PD0-Pad81)") (class "Default")
      (node (ref "U14") (pin "81") (pinfunction "PD0_81") (pintype "unspecified+no_connect"))
    )
    (net (code "134") (name "unconnected-(U14-PD1-Pad82)") (class "Default")
      (node (ref "U14") (pin "82") (pinfunction "PD1_82") (pintype "unspecified+no_connect"))
    )
    (net (code "135") (name "unconnected-(U14-PD2-Pad83)") (class "Default")
      (node (ref "U14") (pin "83") (pinfunction "PD2_83") (pintype "unspecified+no_connect"))
    )
    (net (code "136") (name "unconnected-(U14-PD3-Pad84)") (class "Default")
      (node (ref "U14") (pin "84") (pinfunction "PD3_84") (pintype "unspecified+no_connect"))
    )
    (net (code "137") (name "unconnected-(U14-PD4-Pad85)") (class "Default")
      (node (ref "U14") (pin "85") (pinfunction "PD4_85") (pintype "unspecified+no_connect"))
    )
    (net (code "138") (name "unconnected-(U14-PD7-Pad88)") (class "Default")
      (node (ref "U14") (pin "88") (pinfunction "PD7_88") (pintype "unspecified+no_connect"))
    )
    (net (code "139") (name "unconnected-(U14-PD8-Pad55)") (class "Default")
      (node (ref "U14") (pin "55") (pinfunction "PD8_55") (pintype "unspecified+no_connect"))
    )
    (net (code "140") (name "unconnected-(U14-PD9-Pad56)") (class "Default")
      (node (ref "U14") (pin "56") (pinfunction "PD9_56") (pintype "unspecified+no_connect"))
    )
    (net (code "141") (name "unconnected-(U14-PD10-Pad57)") (class "Default")
      (node (ref "U14") (pin "57") (pinfunction "PD10_57") (pintype "unspecified+no_connect"))
    )
    (net (code "142") (name "unconnected-(U14-PD11-Pad58)") (class "Default")
      (node (ref "U14") (pin "58") (pinfunction "PD11_58") (pintype "unspecified+no_connect"))
    )
    (net (code "143") (name "unconnected-(U14-PD12-Pad59)") (class "Default")
      (node (ref "U14") (pin "59") (pinfunction "PD12_59") (pintype "unspecified+no_connect"))
    )
    (net (code "144") (name "unconnected-(U14-PD13-Pad60)") (class "Default")
      (node (ref "U14") (pin "60") (pinfunction "PD13_60") (pintype "unspecified+no_connect"))
    )
    (net (code "145") (name "unconnected-(U14-PD14-Pad61)") (class "Default")
      (node (ref "U14") (pin "61") (pinfunction "PD14_61") (pintype "unspecified+no_connect"))
    )
    (net (code "146") (name "unconnected-(U14-PD15-Pad62)") (class "Default")
      (node (ref "U14") (pin "62") (pinfunction "PD15_62") (pintype "unspecified+no_connect"))
    )
    (net (code "147") (name "unconnected-(U14-PE0-Pad97)") (class "Default")
      (node (ref "U14") (pin "97") (pinfunction "PE0_97") (pintype "unspecified+no_connect"))
    )
    (net (code "148") (name "unconnected-(U14-PE1-Pad98)") (class "Default")
      (node (ref "U14") (pin "98") (pinfunction "PE1_98") (pintype "unspecified+no_connect"))
    )
    (net (code "149") (name "unconnected-(U14-PE2-Pad1)") (class "Default")
      (node (ref "U14") (pin "1") (pinfunction "PE2_1") (pintype "unspecified+no_connect"))
    )
    (net (code "150") (name "unconnected-(U14-PE3-Pad2)") (class "Default")
      (node (ref "U14") (pin "2") (pinfunction "PE3_2") (pintype "unspecified+no_connect"))
    )
    (net (code "151") (name "unconnected-(U14-PE4-Pad3)") (class "Default")
      (node (ref "U14") (pin "3") (pinfunction "PE4_3") (pintype "unspecified+no_connect"))
    )
    (net (code "152") (name "unconnected-(U14-PE5-Pad4)") (class "Default")
      (node (ref "U14") (pin "4") (pinfunction "PE5_4") (pintype "unspecified+no_connect"))
    )
    (net (code "153") (name "unconnected-(U14-PE6-Pad5)") (class "Default")
      (node (ref "U14") (pin "5") (pinfunction "PE6_5") (pintype "unspecified+no_connect"))
    )
    (net (code "154") (name "unconnected-(U14-PE7-Pad37)") (class "Default")
      (node (ref "U14") (pin "37") (pinfunction "PE7_37") (pintype "unspecified+no_connect"))
    )
    (net (code "155") (name "unconnected-(U14-PE8-Pad38)") (class "Default")
      (node (ref "U14") (pin "38") (pinfunction "PE8_38") (pintype "unspecified+no_connect"))
    )
    (net (code "156") (name "unconnected-(U14-PE9-Pad39)") (class "Default")
      (node (ref "U14") (pin "39") (pinfunction "PE9_39") (pintype "unspecified+no_connect"))
    )
    (net (code "157") (name "unconnected-(U14-PE10-Pad40)") (class "Default")
      (node (ref "U14") (pin "40") (pinfunction "PE10_40") (pintype "unspecified+no_connect"))
    )
    (net (code "158") (name "unconnected-(U14-PE11-Pad41)") (class "Default")
      (node (ref "U14") (pin "41") (pinfunction "PE11_41") (pintype "unspecified+no_connect"))
    )
    (net (code "159") (name "unconnected-(U14-PE12-Pad42)") (class "Default")
      (node (ref "U14") (pin "42") (pinfunction "PE12_42") (pintype "unspecified+no_connect"))
    )
    (net (code "160") (name "unconnected-(U14-PE13-Pad43)") (class "Default")
      (node (ref "U14") (pin "43") (pinfunction "PE13_43") (pintype "unspecified+no_connect"))
    )
    (net (code "161") (name "unconnected-(U14-PE14-Pad44)") (class "Default")
      (node (ref "U14") (pin "44") (pinfunction "PE14_44") (pintype "unspecified+no_connect"))
    )
    (net (code "162") (name "unconnected-(U14-PE15-Pad45)") (class "Default")
      (node (ref "U14") (pin "45") (pinfunction "PE15_45") (pintype "unspecified+no_connect"))
    )
    (net (code "163") (name "unconnected-(U15-IO1-Pad39)") (class "Default")
      (node (ref "U15") (pin "39") (pinfunction "IO1_39") (pintype "unspecified+no_connect"))
    )
    (net (code "164") (name "unconnected-(U15-IO2-Pad38)") (class "Default")
      (node (ref "U15") (pin "38") (pinfunction "IO2_38") (pintype "unspecified+no_connect"))
    )
    (net (code "165") (name "unconnected-(U15-IO3-Pad15)") (class "Default")
      (node (ref "U15") (pin "15") (pinfunction "IO3_15") (pintype "unspecified+no_connect"))
    )
    (net (code "166") (name "unconnected-(U15-IO4-Pad4)") (class "Default")
      (node (ref "U15") (pin "4") (pinfunction "IO4_4") (pintype "unspecified+no_connect"))
    )
    (net (code "167") (name "unconnected-(U15-IO5-Pad5)") (class "Default")
      (node (ref "U15") (pin "5") (pinfunction "IO5_5") (pintype "unspecified+no_connect"))
    )
    (net (code "168") (name "unconnected-(U15-IO9-Pad17)") (class "Default")
      (node (ref "U15") (pin "17") (pinfunction "IO9_17") (pintype "unspecified+no_connect"))
    )
    (net (code "169") (name "unconnected-(U15-IO10-Pad18)") (class "Default")
      (node (ref "U15") (pin "18") (pinfunction "IO10_18") (pintype "unspecified+no_connect"))
    )
    (net (code "170") (name "unconnected-(U15-IO11-Pad19)") (class "Default")
      (node (ref "U15") (pin "19") (pinfunction "IO11_19") (pintype "unspecified+no_connect"))
    )
    (net (code "171") (name "unconnected-(U15-IO12-Pad20)") (class "Default")
      (node (ref "U15") (pin "20") (pinfunction "IO12_20") (pintype "unspecified+no_connect"))
    )
    (net (code "172") (name "unconnected-(U15-IO13-Pad21)") (class "Default")
      (node (ref "U15") (pin "21") (pinfunction "IO13_21") (pintype "unspecified+no_connect"))
    )
    (net (code "173") (name "unconnected-(U15-IO14-Pad22)") (class "Default")
      (node (ref "U15") (pin "22") (pinfunction "IO14_22") (pintype "unspecified+no_connect"))
    )
    (net (code "174") (name "unconnected-(U15-IO18-Pad11)") (class "Default")
      (node (ref "U15") (pin "11") (pinfunction "IO18_11") (pintype "unspecified+no_connect"))
    )
    (net (code "175") (name "unconnected-(U15-IO21-Pad23)") (class "Default")
      (node (ref "U15") (pin "23") (pinfunction "IO21_23") (pintype "unspecified+no_connect"))
    )
    (net (code "176") (name "unconnected-(U15-IO35-Pad28)") (class "Default")
      (node (ref "U15") (pin "28") (pinfunction "IO35_28") (pintype "unspecified+no_connect"))
    )
    (net (code "177") (name "unconnected-(U15-IO36-Pad29)") (class "Default")
      (node (ref "U15") (pin "29") (pinfunction "IO36_29") (pintype "unspecified+no_connect"))
    )
    (net (code "178") (name "unconnected-(U15-IO37-Pad30)") (class "Default")
      (node (ref "U15") (pin "30") (pinfunction "IO37_30") (pintype "unspecified+no_connect"))
    )
    (net (code "179") (name "unconnected-(U15-IO38-Pad31)") (class "Default")
      (node (ref "U15") (pin "31") (pinfunction "IO38_31") (pintype "unspecified+no_connect"))
    )
    (net (code "180") (name "unconnected-(U15-IO39-Pad32)") (class "Default")
      (node (ref "U15") (pin "32") (pinfunction "IO39_32") (pintype "unspecified+no_connect"))
    )
    (net (code "181") (name "unconnected-(U15-IO40-Pad33)") (class "Default")
      (node (ref "U15") (pin "33") (pinfunction "IO40_33") (pintype "unspecified+no_connect"))
    )
    (net (code "182") (name "unconnected-(U15-IO41-Pad34)") (class "Default")
      (node (ref "U15") (pin "34") (pinfunction "IO41_34") (pintype "unspecified+no_connect"))
    )
    (net (code "183") (name "unconnected-(U15-IO42-Pad35)") (class "Default")
      (node (ref "U15") (pin "35") (pinfunction "IO42_35") (pintype "unspecified+no_connect"))
    )
    (net (code "184") (name "unconnected-(U15-IO45-Pad26)") (class "Default")
      (node (ref "U15") (pin "26") (pinfunction "IO45_26") (pintype "unspecified+no_connect"))
    )
    (net (code "185") (name "unconnected-(U15-IO46-Pad16)") (class "Default")
      (node (ref "U15") (pin "16") (pinfunction "IO46_16") (pintype "unspecified+no_connect"))
    )
    (net (code "186") (name "unconnected-(U15-IO47-Pad24)") (class "Default")
      (node (ref "U15") (pin "24") (pinfunction "IO47_24") (pintype "unspecified+no_connect"))
    )
    (net (code "187") (name "unconnected-(U15-IO48-Pad25)") (class "Default")
      (node (ref "U15") (pin "25") (pinfunction "IO48_25") (pintype "unspecified+no_connect"))
    )
    (net (code "188") (name "unconnected-(USB1-SBU1-PadA8)") (class "Default")
      (node (ref "USB1") (pin "A8") (pinfunction "SBU1_A8") (pintype "unspecified+no_connect"))
    )
    (net (code "189") (name "unconnected-(USB1-SBU2-PadB8)") (class "Default")
      (node (ref "USB1") (pin "B8") (pinfunction "SBU2_B8") (pintype "unspecified+no_connect"))
    )
  )
)
